# 24ch_amp.net
KiCad netlist of a schematic drawn in EAGLE
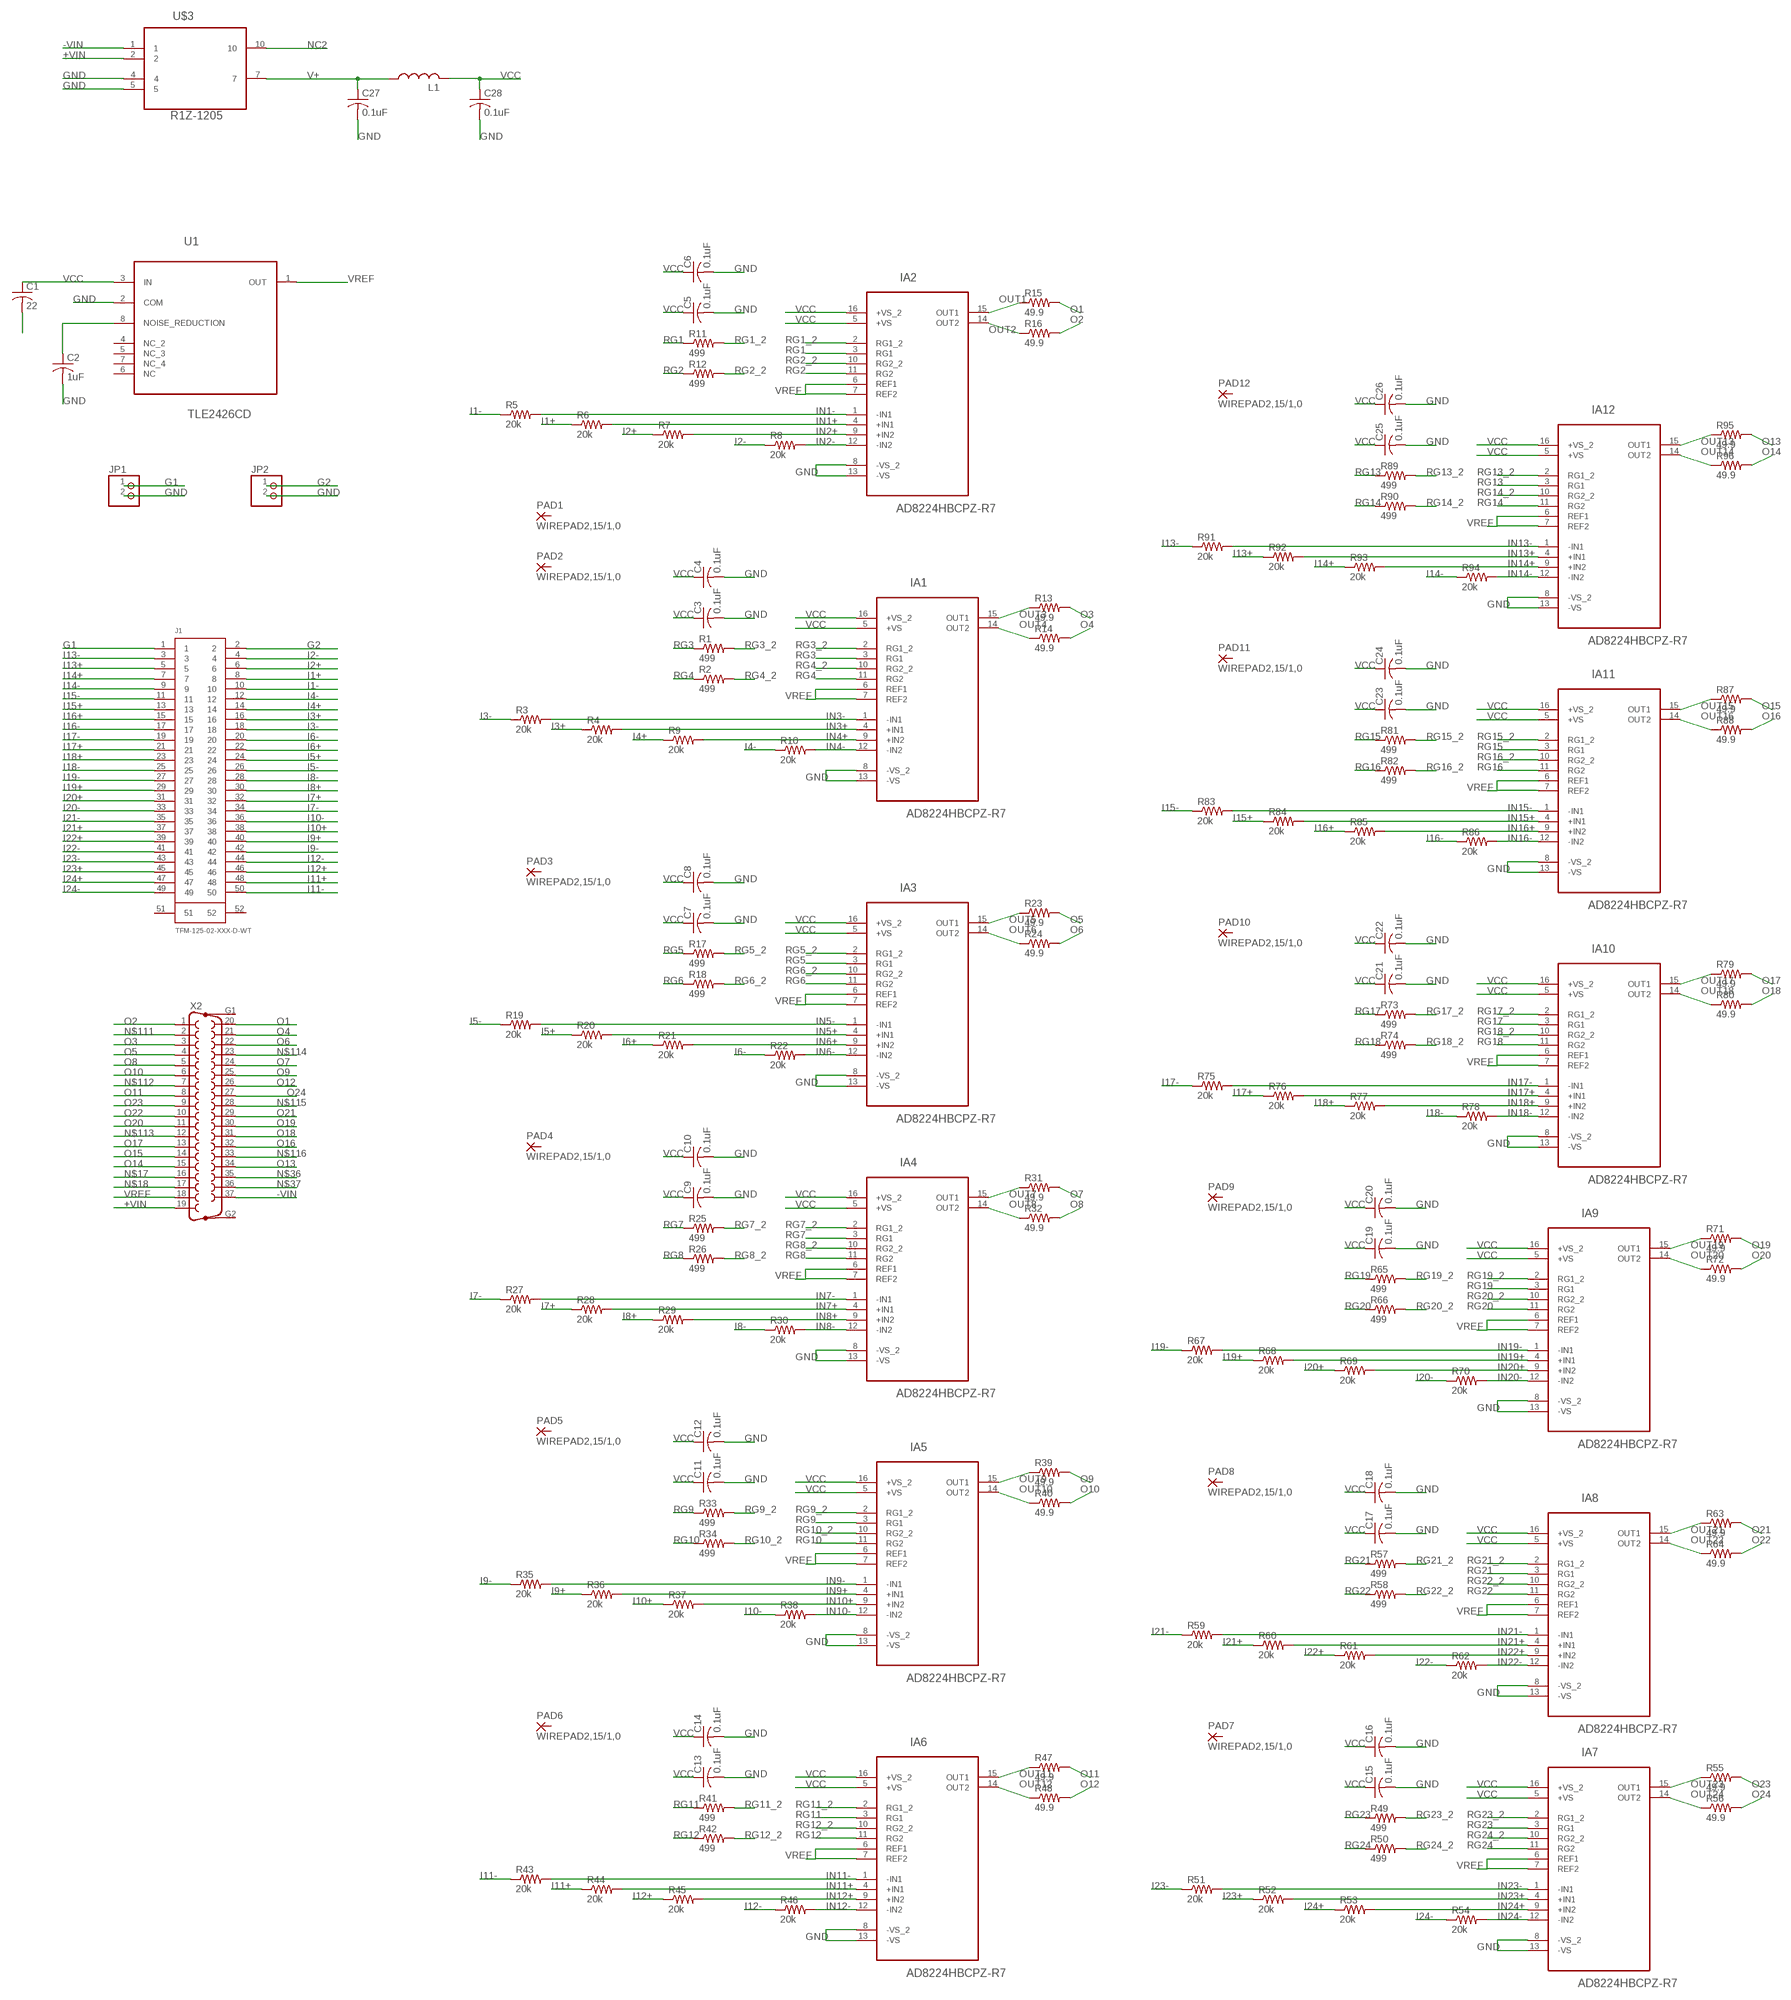
[diagram p0: schematic, sheet 1]

(export (version "E")
  (design (tool "Eeschema 10.0.6"))
  (components
    (comp (ref "C1")
      (value "22")
      (footprint "eagle-import:C0805")
      (libsource (lib "eagle-import") (part "C-USC0805"))
    )
    (comp (ref "C2")
      (value "1uF")
      (footprint "eagle-import:C0805")
      (libsource (lib "eagle-import") (part "C-USC0805"))
    )
    (comp (ref "C3")
      (value "0.1uF")
      (footprint "eagle-import:C0805")
      (libsource (lib "eagle-import") (part "C-USC0805"))
    )
    (comp (ref "C4")
      (value "0.1uF")
      (footprint "eagle-import:C0805")
      (libsource (lib "eagle-import") (part "C-USC0805"))
    )
    (comp (ref "C5")
      (value "0.1uF")
      (footprint "eagle-import:C0805")
      (libsource (lib "eagle-import") (part "C-USC0805"))
    )
    (comp (ref "C6")
      (value "0.1uF")
      (footprint "eagle-import:C0805")
      (libsource (lib "eagle-import") (part "C-USC0805"))
    )
    (comp (ref "C7")
      (value "0.1uF")
      (footprint "eagle-import:C0805")
      (libsource (lib "eagle-import") (part "C-USC0805"))
    )
    (comp (ref "C8")
      (value "0.1uF")
      (footprint "eagle-import:C0805")
      (libsource (lib "eagle-import") (part "C-USC0805"))
    )
    (comp (ref "C9")
      (value "0.1uF")
      (footprint "eagle-import:C0805")
      (libsource (lib "eagle-import") (part "C-USC0805"))
    )
    (comp (ref "C10")
      (value "0.1uF")
      (footprint "eagle-import:C0805")
      (libsource (lib "eagle-import") (part "C-USC0805"))
    )
    (comp (ref "C11")
      (value "0.1uF")
      (footprint "eagle-import:C0805")
      (libsource (lib "eagle-import") (part "C-USC0805"))
    )
    (comp (ref "C12")
      (value "0.1uF")
      (footprint "eagle-import:C0805")
      (libsource (lib "eagle-import") (part "C-USC0805"))
    )
    (comp (ref "C13")
      (value "0.1uF")
      (footprint "eagle-import:C0805")
      (libsource (lib "eagle-import") (part "C-USC0805"))
    )
    (comp (ref "C14")
      (value "0.1uF")
      (footprint "eagle-import:C0805")
      (libsource (lib "eagle-import") (part "C-USC0805"))
    )
    (comp (ref "C15")
      (value "0.1uF")
      (footprint "eagle-import:C0805")
      (libsource (lib "eagle-import") (part "C-USC0805"))
    )
    (comp (ref "C16")
      (value "0.1uF")
      (footprint "eagle-import:C0805")
      (libsource (lib "eagle-import") (part "C-USC0805"))
    )
    (comp (ref "C17")
      (value "0.1uF")
      (footprint "eagle-import:C0805")
      (libsource (lib "eagle-import") (part "C-USC0805"))
    )
    (comp (ref "C18")
      (value "0.1uF")
      (footprint "eagle-import:C0805")
      (libsource (lib "eagle-import") (part "C-USC0805"))
    )
    (comp (ref "C19")
      (value "0.1uF")
      (footprint "eagle-import:C0805")
      (libsource (lib "eagle-import") (part "C-USC0805"))
    )
    (comp (ref "C20")
      (value "0.1uF")
      (footprint "eagle-import:C0805")
      (libsource (lib "eagle-import") (part "C-USC0805"))
    )
    (comp (ref "C21")
      (value "0.1uF")
      (footprint "eagle-import:C0805")
      (libsource (lib "eagle-import") (part "C-USC0805"))
    )
    (comp (ref "C22")
      (value "0.1uF")
      (footprint "eagle-import:C0805")
      (libsource (lib "eagle-import") (part "C-USC0805"))
    )
    (comp (ref "C23")
      (value "0.1uF")
      (footprint "eagle-import:C0805")
      (libsource (lib "eagle-import") (part "C-USC0805"))
    )
    (comp (ref "C24")
      (value "0.1uF")
      (footprint "eagle-import:C0805")
      (libsource (lib "eagle-import") (part "C-USC0805"))
    )
    (comp (ref "C25")
      (value "0.1uF")
      (footprint "eagle-import:C0805")
      (libsource (lib "eagle-import") (part "C-USC0805"))
    )
    (comp (ref "C26")
      (value "0.1uF")
      (footprint "eagle-import:C0805")
      (libsource (lib "eagle-import") (part "C-USC0805"))
    )
    (comp (ref "C27")
      (value "0.1uF")
      (footprint "eagle-import:C0805")
      (libsource (lib "eagle-import") (part "C-USC0805"))
    )
    (comp (ref "C28")
      (value "0.1uF")
      (footprint "eagle-import:C0805")
      (libsource (lib "eagle-import") (part "C-USC0805"))
    )
    (comp (ref "IA1")
      (value "AD8224HBCPZ-R7")
      (footprint "eagle-import:QFN65P400X400X100-16N")
      (libsource (lib "eagle-import") (part "AD8224HBCPZ-R7"))
    )
    (comp (ref "IA2")
      (value "AD8224HBCPZ-R7")
      (footprint "eagle-import:QFN65P400X400X100-16N")
      (libsource (lib "eagle-import") (part "AD8224HBCPZ-R7"))
    )
    (comp (ref "IA3")
      (value "AD8224HBCPZ-R7")
      (footprint "eagle-import:QFN65P400X400X100-16N")
      (libsource (lib "eagle-import") (part "AD8224HBCPZ-R7"))
    )
    (comp (ref "IA4")
      (value "AD8224HBCPZ-R7")
      (footprint "eagle-import:QFN65P400X400X100-16N")
      (libsource (lib "eagle-import") (part "AD8224HBCPZ-R7"))
    )
    (comp (ref "IA5")
      (value "AD8224HBCPZ-R7")
      (footprint "eagle-import:QFN65P400X400X100-16N")
      (libsource (lib "eagle-import") (part "AD8224HBCPZ-R7"))
    )
    (comp (ref "IA6")
      (value "AD8224HBCPZ-R7")
      (footprint "eagle-import:QFN65P400X400X100-16N")
      (libsource (lib "eagle-import") (part "AD8224HBCPZ-R7"))
    )
    (comp (ref "IA7")
      (value "AD8224HBCPZ-R7")
      (footprint "eagle-import:QFN65P400X400X100-16N")
      (libsource (lib "eagle-import") (part "AD8224HBCPZ-R7"))
    )
    (comp (ref "IA8")
      (value "AD8224HBCPZ-R7")
      (footprint "eagle-import:QFN65P400X400X100-16N")
      (libsource (lib "eagle-import") (part "AD8224HBCPZ-R7"))
    )
    (comp (ref "IA9")
      (value "AD8224HBCPZ-R7")
      (footprint "eagle-import:QFN65P400X400X100-16N")
      (libsource (lib "eagle-import") (part "AD8224HBCPZ-R7"))
    )
    (comp (ref "IA10")
      (value "AD8224HBCPZ-R7")
      (footprint "eagle-import:QFN65P400X400X100-16N")
      (libsource (lib "eagle-import") (part "AD8224HBCPZ-R7"))
    )
    (comp (ref "IA11")
      (value "AD8224HBCPZ-R7")
      (footprint "eagle-import:QFN65P400X400X100-16N")
      (libsource (lib "eagle-import") (part "AD8224HBCPZ-R7"))
    )
    (comp (ref "IA12")
      (value "AD8224HBCPZ-R7")
      (footprint "eagle-import:QFN65P400X400X100-16N")
      (libsource (lib "eagle-import") (part "AD8224HBCPZ-R7"))
    )
    (comp (ref "J1")
      (value "TFM-125-02-XXX-D-WT")
      (footprint "eagle-import:TFM-125-02-XXX-D-WT")
      (libsource (lib "eagle-import") (part "TFM-125-02-XXX-D-WT"))
    )
    (comp (ref "JP1")
      (value "PINHD-1X2")
      (footprint "eagle-import:1X02")
      (libsource (lib "eagle-import") (part "PINHD-1X2"))
    )
    (comp (ref "JP2")
      (value "PINHD-1X2")
      (footprint "eagle-import:1X02")
      (libsource (lib "eagle-import") (part "PINHD-1X2"))
    )
    (comp (ref "L1")
      (value "L-USL3225M")
      (footprint "eagle-import:L3225M")
      (libsource (lib "eagle-import") (part "L-USL3225M"))
    )
    (comp (ref "PAD1")
      (value "WIREPAD2,15/1,0")
      (footprint "eagle-import:2,15_1,0")
      (libsource (lib "eagle-import") (part "WIREPAD2,15/1,0"))
    )
    (comp (ref "PAD2")
      (value "WIREPAD2,15/1,0")
      (footprint "eagle-import:2,15_1,0")
      (libsource (lib "eagle-import") (part "WIREPAD2,15/1,0"))
    )
    (comp (ref "PAD3")
      (value "WIREPAD2,15/1,0")
      (footprint "eagle-import:2,15_1,0")
      (libsource (lib "eagle-import") (part "WIREPAD2,15/1,0"))
    )
    (comp (ref "PAD4")
      (value "WIREPAD2,15/1,0")
      (footprint "eagle-import:2,15_1,0")
      (libsource (lib "eagle-import") (part "WIREPAD2,15/1,0"))
    )
    (comp (ref "PAD5")
      (value "WIREPAD2,15/1,0")
      (footprint "eagle-import:2,15_1,0")
      (libsource (lib "eagle-import") (part "WIREPAD2,15/1,0"))
    )
    (comp (ref "PAD6")
      (value "WIREPAD2,15/1,0")
      (footprint "eagle-import:2,15_1,0")
      (libsource (lib "eagle-import") (part "WIREPAD2,15/1,0"))
    )
    (comp (ref "PAD7")
      (value "WIREPAD2,15/1,0")
      (footprint "eagle-import:2,15_1,0")
      (libsource (lib "eagle-import") (part "WIREPAD2,15/1,0"))
    )
    (comp (ref "PAD8")
      (value "WIREPAD2,15/1,0")
      (footprint "eagle-import:2,15_1,0")
      (libsource (lib "eagle-import") (part "WIREPAD2,15/1,0"))
    )
    (comp (ref "PAD9")
      (value "WIREPAD2,15/1,0")
      (footprint "eagle-import:2,15_1,0")
      (libsource (lib "eagle-import") (part "WIREPAD2,15/1,0"))
    )
    (comp (ref "PAD10")
      (value "WIREPAD2,15/1,0")
      (footprint "eagle-import:2,15_1,0")
      (libsource (lib "eagle-import") (part "WIREPAD2,15/1,0"))
    )
    (comp (ref "PAD11")
      (value "WIREPAD2,15/1,0")
      (footprint "eagle-import:2,15_1,0")
      (libsource (lib "eagle-import") (part "WIREPAD2,15/1,0"))
    )
    (comp (ref "PAD12")
      (value "WIREPAD2,15/1,0")
      (footprint "eagle-import:2,15_1,0")
      (libsource (lib "eagle-import") (part "WIREPAD2,15/1,0"))
    )
    (comp (ref "R1")
      (value "499")
      (footprint "eagle-import:R0805")
      (libsource (lib "eagle-import") (part "R-US_R0805"))
    )
    (comp (ref "R2")
      (value "499")
      (footprint "eagle-import:R0805")
      (libsource (lib "eagle-import") (part "R-US_R0805"))
    )
    (comp (ref "R3")
      (value "20k")
      (footprint "eagle-import:R0805")
      (libsource (lib "eagle-import") (part "R-US_R0805"))
    )
    (comp (ref "R4")
      (value "20k")
      (footprint "eagle-import:R0805")
      (libsource (lib "eagle-import") (part "R-US_R0805"))
    )
    (comp (ref "R5")
      (value "20k")
      (footprint "eagle-import:R0805")
      (libsource (lib "eagle-import") (part "R-US_R0805"))
    )
    (comp (ref "R6")
      (value "20k")
      (footprint "eagle-import:R0805")
      (libsource (lib "eagle-import") (part "R-US_R0805"))
    )
    (comp (ref "R7")
      (value "20k")
      (footprint "eagle-import:R0805")
      (libsource (lib "eagle-import") (part "R-US_R0805"))
    )
    (comp (ref "R8")
      (value "20k")
      (footprint "eagle-import:R0805")
      (libsource (lib "eagle-import") (part "R-US_R0805"))
    )
    (comp (ref "R9")
      (value "20k")
      (footprint "eagle-import:R0805")
      (libsource (lib "eagle-import") (part "R-US_R0805"))
    )
    (comp (ref "R10")
      (value "20k")
      (footprint "eagle-import:R0805")
      (libsource (lib "eagle-import") (part "R-US_R0805"))
    )
    (comp (ref "R11")
      (value "499")
      (footprint "eagle-import:R0805")
      (libsource (lib "eagle-import") (part "R-US_R0805"))
    )
    (comp (ref "R12")
      (value "499")
      (footprint "eagle-import:R0805")
      (libsource (lib "eagle-import") (part "R-US_R0805"))
    )
    (comp (ref "R13")
      (value "49.9")
      (footprint "eagle-import:R0805")
      (libsource (lib "eagle-import") (part "R-US_R0805"))
    )
    (comp (ref "R14")
      (value "49.9")
      (footprint "eagle-import:R0805")
      (libsource (lib "eagle-import") (part "R-US_R0805"))
    )
    (comp (ref "R15")
      (value "49.9")
      (footprint "eagle-import:R0805")
      (libsource (lib "eagle-import") (part "R-US_R0805"))
    )
    (comp (ref "R16")
      (value "49.9")
      (footprint "eagle-import:R0805")
      (libsource (lib "eagle-import") (part "R-US_R0805"))
    )
    (comp (ref "R17")
      (value "499")
      (footprint "eagle-import:R0805")
      (libsource (lib "eagle-import") (part "R-US_R0805"))
    )
    (comp (ref "R18")
      (value "499")
      (footprint "eagle-import:R0805")
      (libsource (lib "eagle-import") (part "R-US_R0805"))
    )
    (comp (ref "R19")
      (value "20k")
      (footprint "eagle-import:R0805")
      (libsource (lib "eagle-import") (part "R-US_R0805"))
    )
    (comp (ref "R20")
      (value "20k")
      (footprint "eagle-import:R0805")
      (libsource (lib "eagle-import") (part "R-US_R0805"))
    )
    (comp (ref "R21")
      (value "20k")
      (footprint "eagle-import:R0805")
      (libsource (lib "eagle-import") (part "R-US_R0805"))
    )
    (comp (ref "R22")
      (value "20k")
      (footprint "eagle-import:R0805")
      (libsource (lib "eagle-import") (part "R-US_R0805"))
    )
    (comp (ref "R23")
      (value "49.9")
      (footprint "eagle-import:R0805")
      (libsource (lib "eagle-import") (part "R-US_R0805"))
    )
    (comp (ref "R24")
      (value "49.9")
      (footprint "eagle-import:R0805")
      (libsource (lib "eagle-import") (part "R-US_R0805"))
    )
    (comp (ref "R25")
      (value "499")
      (footprint "eagle-import:R0805")
      (libsource (lib "eagle-import") (part "R-US_R0805"))
    )
    (comp (ref "R26")
      (value "499")
      (footprint "eagle-import:R0805")
      (libsource (lib "eagle-import") (part "R-US_R0805"))
    )
    (comp (ref "R27")
      (value "20k")
      (footprint "eagle-import:R0805")
      (libsource (lib "eagle-import") (part "R-US_R0805"))
    )
    (comp (ref "R28")
      (value "20k")
      (footprint "eagle-import:R0805")
      (libsource (lib "eagle-import") (part "R-US_R0805"))
    )
    (comp (ref "R29")
      (value "20k")
      (footprint "eagle-import:R0805")
      (libsource (lib "eagle-import") (part "R-US_R0805"))
    )
    (comp (ref "R30")
      (value "20k")
      (footprint "eagle-import:R0805")
      (libsource (lib "eagle-import") (part "R-US_R0805"))
    )
    (comp (ref "R31")
      (value "49.9")
      (footprint "eagle-import:R0805")
      (libsource (lib "eagle-import") (part "R-US_R0805"))
    )
    (comp (ref "R32")
      (value "49.9")
      (footprint "eagle-import:R0805")
      (libsource (lib "eagle-import") (part "R-US_R0805"))
    )
    (comp (ref "R33")
      (value "499")
      (footprint "eagle-import:R0805")
      (libsource (lib "eagle-import") (part "R-US_R0805"))
    )
    (comp (ref "R34")
      (value "499")
      (footprint "eagle-import:R0805")
      (libsource (lib "eagle-import") (part "R-US_R0805"))
    )
    (comp (ref "R35")
      (value "20k")
      (footprint "eagle-import:R0805")
      (libsource (lib "eagle-import") (part "R-US_R0805"))
    )
    (comp (ref "R36")
      (value "20k")
      (footprint "eagle-import:R0805")
      (libsource (lib "eagle-import") (part "R-US_R0805"))
    )
    (comp (ref "R37")
      (value "20k")
      (footprint "eagle-import:R0805")
      (libsource (lib "eagle-import") (part "R-US_R0805"))
    )
    (comp (ref "R38")
      (value "20k")
      (footprint "eagle-import:R0805")
      (libsource (lib "eagle-import") (part "R-US_R0805"))
    )
    (comp (ref "R39")
      (value "49.9")
      (footprint "eagle-import:R0805")
      (libsource (lib "eagle-import") (part "R-US_R0805"))
    )
    (comp (ref "R40")
      (value "49.9")
      (footprint "eagle-import:R0805")
      (libsource (lib "eagle-import") (part "R-US_R0805"))
    )
    (comp (ref "R41")
      (value "499")
      (footprint "eagle-import:R0805")
      (libsource (lib "eagle-import") (part "R-US_R0805"))
    )
    (comp (ref "R42")
      (value "499")
      (footprint "eagle-import:R0805")
      (libsource (lib "eagle-import") (part "R-US_R0805"))
    )
    (comp (ref "R43")
      (value "20k")
      (footprint "eagle-import:R0805")
      (libsource (lib "eagle-import") (part "R-US_R0805"))
    )
    (comp (ref "R44")
      (value "20k")
      (footprint "eagle-import:R0805")
      (libsource (lib "eagle-import") (part "R-US_R0805"))
    )
    (comp (ref "R45")
      (value "20k")
      (footprint "eagle-import:R0805")
      (libsource (lib "eagle-import") (part "R-US_R0805"))
    )
    (comp (ref "R46")
      (value "20k")
      (footprint "eagle-import:R0805")
      (libsource (lib "eagle-import") (part "R-US_R0805"))
    )
    (comp (ref "R47")
      (value "49.9")
      (footprint "eagle-import:R0805")
      (libsource (lib "eagle-import") (part "R-US_R0805"))
    )
    (comp (ref "R48")
      (value "49.9")
      (footprint "eagle-import:R0805")
      (libsource (lib "eagle-import") (part "R-US_R0805"))
    )
    (comp (ref "R49")
      (value "499")
      (footprint "eagle-import:R0805")
      (libsource (lib "eagle-import") (part "R-US_R0805"))
    )
    (comp (ref "R50")
      (value "499")
      (footprint "eagle-import:R0805")
      (libsource (lib "eagle-import") (part "R-US_R0805"))
    )
    (comp (ref "R51")
      (value "20k")
      (footprint "eagle-import:R0805")
      (libsource (lib "eagle-import") (part "R-US_R0805"))
    )
    (comp (ref "R52")
      (value "20k")
      (footprint "eagle-import:R0805")
      (libsource (lib "eagle-import") (part "R-US_R0805"))
    )
    (comp (ref "R53")
      (value "20k")
      (footprint "eagle-import:R0805")
      (libsource (lib "eagle-import") (part "R-US_R0805"))
    )
    (comp (ref "R54")
      (value "20k")
      (footprint "eagle-import:R0805")
      (libsource (lib "eagle-import") (part "R-US_R0805"))
    )
    (comp (ref "R55")
      (value "49.9")
      (footprint "eagle-import:R0805")
      (libsource (lib "eagle-import") (part "R-US_R0805"))
    )
    (comp (ref "R56")
      (value "49.9")
      (footprint "eagle-import:R0805")
      (libsource (lib "eagle-import") (part "R-US_R0805"))
    )
    (comp (ref "R57")
      (value "499")
      (footprint "eagle-import:R0805")
      (libsource (lib "eagle-import") (part "R-US_R0805"))
    )
    (comp (ref "R58")
      (value "499")
      (footprint "eagle-import:R0805")
      (libsource (lib "eagle-import") (part "R-US_R0805"))
    )
    (comp (ref "R59")
      (value "20k")
      (footprint "eagle-import:R0805")
      (libsource (lib "eagle-import") (part "R-US_R0805"))
    )
    (comp (ref "R60")
      (value "20k")
      (footprint "eagle-import:R0805")
      (libsource (lib "eagle-import") (part "R-US_R0805"))
    )
    (comp (ref "R61")
      (value "20k")
      (footprint "eagle-import:R0805")
      (libsource (lib "eagle-import") (part "R-US_R0805"))
    )
    (comp (ref "R62")
      (value "20k")
      (footprint "eagle-import:R0805")
      (libsource (lib "eagle-import") (part "R-US_R0805"))
    )
    (comp (ref "R63")
      (value "49.9")
      (footprint "eagle-import:R0805")
      (libsource (lib "eagle-import") (part "R-US_R0805"))
    )
    (comp (ref "R64")
      (value "49.9")
      (footprint "eagle-import:R0805")
      (libsource (lib "eagle-import") (part "R-US_R0805"))
    )
    (comp (ref "R65")
      (value "499")
      (footprint "eagle-import:R0805")
      (libsource (lib "eagle-import") (part "R-US_R0805"))
    )
    (comp (ref "R66")
      (value "499")
      (footprint "eagle-import:R0805")
      (libsource (lib "eagle-import") (part "R-US_R0805"))
    )
    (comp (ref "R67")
      (value "20k")
      (footprint "eagle-import:R0805")
      (libsource (lib "eagle-import") (part "R-US_R0805"))
    )
    (comp (ref "R68")
      (value "20k")
      (footprint "eagle-import:R0805")
      (libsource (lib "eagle-import") (part "R-US_R0805"))
    )
    (comp (ref "R69")
      (value "20k")
      (footprint "eagle-import:R0805")
      (libsource (lib "eagle-import") (part "R-US_R0805"))
    )
    (comp (ref "R70")
      (value "20k")
      (footprint "eagle-import:R0805")
      (libsource (lib "eagle-import") (part "R-US_R0805"))
    )
    (comp (ref "R71")
      (value "49.9")
      (footprint "eagle-import:R0805")
      (libsource (lib "eagle-import") (part "R-US_R0805"))
    )
    (comp (ref "R72")
      (value "49.9")
      (footprint "eagle-import:R0805")
      (libsource (lib "eagle-import") (part "R-US_R0805"))
    )
    (comp (ref "R73")
      (value "499")
      (footprint "eagle-import:R0805")
      (libsource (lib "eagle-import") (part "R-US_R0805"))
    )
    (comp (ref "R74")
      (value "499")
      (footprint "eagle-import:R0805")
      (libsource (lib "eagle-import") (part "R-US_R0805"))
    )
    (comp (ref "R75")
      (value "20k")
      (footprint "eagle-import:R0805")
      (libsource (lib "eagle-import") (part "R-US_R0805"))
    )
    (comp (ref "R76")
      (value "20k")
      (footprint "eagle-import:R0805")
      (libsource (lib "eagle-import") (part "R-US_R0805"))
    )
    (comp (ref "R77")
      (value "20k")
      (footprint "eagle-import:R0805")
      (libsource (lib "eagle-import") (part "R-US_R0805"))
    )
    (comp (ref "R78")
      (value "20k")
      (footprint "eagle-import:R0805")
      (libsource (lib "eagle-import") (part "R-US_R0805"))
    )
    (comp (ref "R79")
      (value "49.9")
      (footprint "eagle-import:R0805")
      (libsource (lib "eagle-import") (part "R-US_R0805"))
    )
    (comp (ref "R80")
      (value "49.9")
      (footprint "eagle-import:R0805")
      (libsource (lib "eagle-import") (part "R-US_R0805"))
    )
    (comp (ref "R81")
      (value "499")
      (footprint "eagle-import:R0805")
      (libsource (lib "eagle-import") (part "R-US_R0805"))
    )
    (comp (ref "R82")
      (value "499")
      (footprint "eagle-import:R0805")
      (libsource (lib "eagle-import") (part "R-US_R0805"))
    )
    (comp (ref "R83")
      (value "20k")
      (footprint "eagle-import:R0805")
      (libsource (lib "eagle-import") (part "R-US_R0805"))
    )
    (comp (ref "R84")
      (value "20k")
      (footprint "eagle-import:R0805")
      (libsource (lib "eagle-import") (part "R-US_R0805"))
    )
    (comp (ref "R85")
      (value "20k")
      (footprint "eagle-import:R0805")
      (libsource (lib "eagle-import") (part "R-US_R0805"))
    )
    (comp (ref "R86")
      (value "20k")
      (footprint "eagle-import:R0805")
      (libsource (lib "eagle-import") (part "R-US_R0805"))
    )
    (comp (ref "R87")
      (value "49.9")
      (footprint "eagle-import:R0805")
      (libsource (lib "eagle-import") (part "R-US_R0805"))
    )
    (comp (ref "R88")
      (value "49.9")
      (footprint "eagle-import:R0805")
      (libsource (lib "eagle-import") (part "R-US_R0805"))
    )
    (comp (ref "R89")
      (value "499")
      (footprint "eagle-import:R0805")
      (libsource (lib "eagle-import") (part "R-US_R0805"))
    )
    (comp (ref "R90")
      (value "499")
      (footprint "eagle-import:R0805")
      (libsource (lib "eagle-import") (part "R-US_R0805"))
    )
    (comp (ref "R91")
      (value "20k")
      (footprint "eagle-import:R0805")
      (libsource (lib "eagle-import") (part "R-US_R0805"))
    )
    (comp (ref "R92")
      (value "20k")
      (footprint "eagle-import:R0805")
      (libsource (lib "eagle-import") (part "R-US_R0805"))
    )
    (comp (ref "R93")
      (value "20k")
      (footprint "eagle-import:R0805")
      (libsource (lib "eagle-import") (part "R-US_R0805"))
    )
    (comp (ref "R94")
      (value "20k")
      (footprint "eagle-import:R0805")
      (libsource (lib "eagle-import") (part "R-US_R0805"))
    )
    (comp (ref "R95")
      (value "49.9")
      (footprint "eagle-import:R0805")
      (libsource (lib "eagle-import") (part "R-US_R0805"))
    )
    (comp (ref "R96")
      (value "49.9")
      (footprint "eagle-import:R0805")
      (libsource (lib "eagle-import") (part "R-US_R0805"))
    )
    (comp (ref "U$3")
      (value "R1Z-1205")
      (footprint "eagle-import:R1Z-1205")
      (libsource (lib "eagle-import") (part "R1Z-1205"))
    )
    (comp (ref "U1")
      (value "TLE2426CD")
      (footprint "eagle-import:SOIC127P600X175-8N")
      (libsource (lib "eagle-import") (part "TLE2426CD"))
    )
    (comp (ref "X2")
      (value "F37HP")
      (footprint "eagle-import:F37HP")
      (libsource (lib "eagle-import") (part "F37HP"))
    )
  )
  (nets
    (net (code "1") (name "/+VIN") (class "Default")
      (node (ref "U$3") (pin "2") (pinfunction "2_2") (pintype "passive"))
      (node (ref "X2") (pin "19") (pinfunction "19_19") (pintype "passive"))
    )
    (net (code "2") (name "/-VIN") (class "Default")
      (node (ref "U$3") (pin "1") (pinfunction "1_1") (pintype "passive"))
      (node (ref "X2") (pin "37") (pinfunction "37_37") (pintype "passive"))
    )
    (net (code "3") (name "/G1") (class "Default")
      (node (ref "J1") (pin "1") (pinfunction "1_1") (pintype "bidirectional"))
      (node (ref "JP1") (pin "1") (pinfunction "1_1") (pintype "passive"))
    )
    (net (code "4") (name "/G2") (class "Default")
      (node (ref "J1") (pin "2") (pinfunction "2_2") (pintype "bidirectional"))
      (node (ref "JP2") (pin "1") (pinfunction "1_1") (pintype "passive"))
    )
    (net (code "5") (name "/GND") (class "Default")
      (node (ref "C1") (pin "2") (pinfunction "2_2") (pintype "passive"))
      (node (ref "C10") (pin "2") (pinfunction "2_2") (pintype "passive"))
      (node (ref "C11") (pin "2") (pinfunction "2_2") (pintype "passive"))
      (node (ref "C12") (pin "2") (pinfunction "2_2") (pintype "passive"))
      (node (ref "C13") (pin "2") (pinfunction "2_2") (pintype "passive"))
      (node (ref "C14") (pin "2") (pinfunction "2_2") (pintype "passive"))
      (node (ref "C15") (pin "2") (pinfunction "2_2") (pintype "passive"))
      (node (ref "C16") (pin "2") (pinfunction "2_2") (pintype "passive"))
      (node (ref "C17") (pin "2") (pinfunction "2_2") (pintype "passive"))
      (node (ref "C18") (pin "2") (pinfunction "2_2") (pintype "passive"))
      (node (ref "C19") (pin "2") (pinfunction "2_2") (pintype "passive"))
      (node (ref "C2") (pin "2") (pinfunction "2_2") (pintype "passive"))
      (node (ref "C20") (pin "2") (pinfunction "2_2") (pintype "passive"))
      (node (ref "C21") (pin "2") (pinfunction "2_2") (pintype "passive"))
      (node (ref "C22") (pin "2") (pinfunction "2_2") (pintype "passive"))
      (node (ref "C23") (pin "2") (pinfunction "2_2") (pintype "passive"))
      (node (ref "C24") (pin "2") (pinfunction "2_2") (pintype "passive"))
      (node (ref "C25") (pin "2") (pinfunction "2_2") (pintype "passive"))
      (node (ref "C26") (pin "2") (pinfunction "2_2") (pintype "passive"))
      (node (ref "C27") (pin "2") (pinfunction "2_2") (pintype "passive"))
      (node (ref "C28") (pin "2") (pinfunction "2_2") (pintype "passive"))
      (node (ref "C3") (pin "2") (pinfunction "2_2") (pintype "passive"))
      (node (ref "C4") (pin "2") (pinfunction "2_2") (pintype "passive"))
      (node (ref "C5") (pin "2") (pinfunction "2_2") (pintype "passive"))
      (node (ref "C6") (pin "2") (pinfunction "2_2") (pintype "passive"))
      (node (ref "C7") (pin "2") (pinfunction "2_2") (pintype "passive"))
      (node (ref "C8") (pin "2") (pinfunction "2_2") (pintype "passive"))
      (node (ref "C9") (pin "2") (pinfunction "2_2") (pintype "passive"))
      (node (ref "IA1") (pin "13") (pinfunction "-VS_13") (pintype "power_in"))
      (node (ref "IA1") (pin "8") (pinfunction "-VS_2_8") (pintype "power_in"))
      (node (ref "IA10") (pin "13") (pinfunction "-VS_13") (pintype "power_in"))
      (node (ref "IA10") (pin "8") (pinfunction "-VS_2_8") (pintype "power_in"))
      (node (ref "IA11") (pin "13") (pinfunction "-VS_13") (pintype "power_in"))
      (node (ref "IA11") (pin "8") (pinfunction "-VS_2_8") (pintype "power_in"))
      (node (ref "IA12") (pin "13") (pinfunction "-VS_13") (pintype "power_in"))
      (node (ref "IA12") (pin "8") (pinfunction "-VS_2_8") (pintype "power_in"))
      (node (ref "IA2") (pin "13") (pinfunction "-VS_13") (pintype "power_in"))
      (node (ref "IA2") (pin "8") (pinfunction "-VS_2_8") (pintype "power_in"))
      (node (ref "IA3") (pin "13") (pinfunction "-VS_13") (pintype "power_in"))
      (node (ref "IA3") (pin "8") (pinfunction "-VS_2_8") (pintype "power_in"))
      (node (ref "IA4") (pin "13") (pinfunction "-VS_13") (pintype "power_in"))
      (node (ref "IA4") (pin "8") (pinfunction "-VS_2_8") (pintype "power_in"))
      (node (ref "IA5") (pin "13") (pinfunction "-VS_13") (pintype "power_in"))
      (node (ref "IA5") (pin "8") (pinfunction "-VS_2_8") (pintype "power_in"))
      (node (ref "IA6") (pin "13") (pinfunction "-VS_13") (pintype "power_in"))
      (node (ref "IA6") (pin "8") (pinfunction "-VS_2_8") (pintype "power_in"))
      (node (ref "IA7") (pin "13") (pinfunction "-VS_13") (pintype "power_in"))
      (node (ref "IA7") (pin "8") (pinfunction "-VS_2_8") (pintype "power_in"))
      (node (ref "IA8") (pin "13") (pinfunction "-VS_13") (pintype "power_in"))
      (node (ref "IA8") (pin "8") (pinfunction "-VS_2_8") (pintype "power_in"))
      (node (ref "IA9") (pin "13") (pinfunction "-VS_13") (pintype "power_in"))
      (node (ref "IA9") (pin "8") (pinfunction "-VS_2_8") (pintype "power_in"))
      (node (ref "JP1") (pin "2") (pinfunction "2_2") (pintype "passive"))
      (node (ref "JP2") (pin "2") (pinfunction "2_2") (pintype "passive"))
      (node (ref "U$3") (pin "4") (pinfunction "4_4") (pintype "passive"))
      (node (ref "U$3") (pin "5") (pinfunction "5_5") (pintype "passive"))
      (node (ref "U1") (pin "2") (pinfunction "COM_2") (pintype "passive"))
    )
    (net (code "6") (name "/I1+") (class "Default")
      (node (ref "J1") (pin "8") (pinfunction "8_8") (pintype "bidirectional"))
      (node (ref "R6") (pin "1") (pinfunction "1_1") (pintype "passive"))
    )
    (net (code "7") (name "/I1-") (class "Default")
      (node (ref "J1") (pin "10") (pinfunction "10_10") (pintype "bidirectional"))
      (node (ref "R5") (pin "1") (pinfunction "1_1") (pintype "passive"))
    )
    (net (code "8") (name "/I2+") (class "Default")
      (node (ref "J1") (pin "6") (pinfunction "6_6") (pintype "bidirectional"))
      (node (ref "R7") (pin "1") (pinfunction "1_1") (pintype "passive"))
    )
    (net (code "9") (name "/I2-") (class "Default")
      (node (ref "J1") (pin "4") (pinfunction "4_4") (pintype "bidirectional"))
      (node (ref "R8") (pin "1") (pinfunction "1_1") (pintype "passive"))
    )
    (net (code "10") (name "/I3+") (class "Default")
      (node (ref "J1") (pin "16") (pinfunction "16_16") (pintype "bidirectional"))
      (node (ref "R4") (pin "1") (pinfunction "1_1") (pintype "passive"))
    )
    (net (code "11") (name "/I3-") (class "Default")
      (node (ref "J1") (pin "18") (pinfunction "18_18") (pintype "bidirectional"))
      (node (ref "R3") (pin "1") (pinfunction "1_1") (pintype "passive"))
    )
    (net (code "12") (name "/I4+") (class "Default")
      (node (ref "J1") (pin "14") (pinfunction "14_14") (pintype "bidirectional"))
      (node (ref "R9") (pin "1") (pinfunction "1_1") (pintype "passive"))
    )
    (net (code "13") (name "/I4-") (class "Default")
      (node (ref "J1") (pin "12") (pinfunction "12_12") (pintype "bidirectional"))
      (node (ref "R10") (pin "1") (pinfunction "1_1") (pintype "passive"))
    )
    (net (code "14") (name "/I5+") (class "Default")
      (node (ref "J1") (pin "24") (pinfunction "24_24") (pintype "bidirectional"))
      (node (ref "R20") (pin "1") (pinfunction "1_1") (pintype "passive"))
    )
    (net (code "15") (name "/I5-") (class "Default")
      (node (ref "J1") (pin "26") (pinfunction "26_26") (pintype "bidirectional"))
      (node (ref "R19") (pin "1") (pinfunction "1_1") (pintype "passive"))
    )
    (net (code "16") (name "/I6+") (class "Default")
      (node (ref "J1") (pin "22") (pinfunction "22_22") (pintype "bidirectional"))
      (node (ref "R21") (pin "1") (pinfunction "1_1") (pintype "passive"))
    )
    (net (code "17") (name "/I6-") (class "Default")
      (node (ref "J1") (pin "20") (pinfunction "20_20") (pintype "bidirectional"))
      (node (ref "R22") (pin "1") (pinfunction "1_1") (pintype "passive"))
    )
    (net (code "18") (name "/I7+") (class "Default")
      (node (ref "J1") (pin "32") (pinfunction "32_32") (pintype "bidirectional"))
      (node (ref "R28") (pin "1") (pinfunction "1_1") (pintype "passive"))
    )
    (net (code "19") (name "/I7-") (class "Default")
      (node (ref "J1") (pin "34") (pinfunction "34_34") (pintype "bidirectional"))
      (node (ref "R27") (pin "1") (pinfunction "1_1") (pintype "passive"))
    )
    (net (code "20") (name "/I8+") (class "Default")
      (node (ref "J1") (pin "30") (pinfunction "30_30") (pintype "bidirectional"))
      (node (ref "R29") (pin "1") (pinfunction "1_1") (pintype "passive"))
    )
    (net (code "21") (name "/I8-") (class "Default")
      (node (ref "J1") (pin "28") (pinfunction "28_28") (pintype "bidirectional"))
      (node (ref "R30") (pin "1") (pinfunction "1_1") (pintype "passive"))
    )
    (net (code "22") (name "/I9+") (class "Default")
      (node (ref "J1") (pin "40") (pinfunction "40_40") (pintype "bidirectional"))
      (node (ref "R36") (pin "1") (pinfunction "1_1") (pintype "passive"))
    )
    (net (code "23") (name "/I9-") (class "Default")
      (node (ref "J1") (pin "42") (pinfunction "42_42") (pintype "bidirectional"))
      (node (ref "R35") (pin "1") (pinfunction "1_1") (pintype "passive"))
    )
    (net (code "24") (name "/I10+") (class "Default")
      (node (ref "J1") (pin "38") (pinfunction "38_38") (pintype "bidirectional"))
      (node (ref "R37") (pin "1") (pinfunction "1_1") (pintype "passive"))
    )
    (net (code "25") (name "/I10-") (class "Default")
      (node (ref "J1") (pin "36") (pinfunction "36_36") (pintype "bidirectional"))
      (node (ref "R38") (pin "1") (pinfunction "1_1") (pintype "passive"))
    )
    (net (code "26") (name "/I11+") (class "Default")
      (node (ref "J1") (pin "48") (pinfunction "48_48") (pintype "bidirectional"))
      (node (ref "R44") (pin "1") (pinfunction "1_1") (pintype "passive"))
    )
    (net (code "27") (name "/I11-") (class "Default")
      (node (ref "J1") (pin "50") (pinfunction "50_50") (pintype "bidirectional"))
      (node (ref "R43") (pin "1") (pinfunction "1_1") (pintype "passive"))
    )
    (net (code "28") (name "/I12+") (class "Default")
      (node (ref "J1") (pin "46") (pinfunction "46_46") (pintype "bidirectional"))
      (node (ref "R45") (pin "1") (pinfunction "1_1") (pintype "passive"))
    )
    (net (code "29") (name "/I12-") (class "Default")
      (node (ref "J1") (pin "44") (pinfunction "44_44") (pintype "bidirectional"))
      (node (ref "R46") (pin "1") (pinfunction "1_1") (pintype "passive"))
    )
    (net (code "30") (name "/I13+") (class "Default")
      (node (ref "J1") (pin "5") (pinfunction "5_5") (pintype "bidirectional"))
      (node (ref "R92") (pin "1") (pinfunction "1_1") (pintype "passive"))
    )
    (net (code "31") (name "/I13-") (class "Default")
      (node (ref "J1") (pin "3") (pinfunction "3_3") (pintype "bidirectional"))
      (node (ref "R91") (pin "1") (pinfunction "1_1") (pintype "passive"))
    )
    (net (code "32") (name "/I14+") (class "Default")
      (node (ref "J1") (pin "7") (pinfunction "7_7") (pintype "bidirectional"))
      (node (ref "R93") (pin "1") (pinfunction "1_1") (pintype "passive"))
    )
    (net (code "33") (name "/I14-") (class "Default")
      (node (ref "J1") (pin "9") (pinfunction "9_9") (pintype "bidirectional"))
      (node (ref "R94") (pin "1") (pinfunction "1_1") (pintype "passive"))
    )
    (net (code "34") (name "/I15+") (class "Default")
      (node (ref "J1") (pin "13") (pinfunction "13_13") (pintype "bidirectional"))
      (node (ref "R84") (pin "1") (pinfunction "1_1") (pintype "passive"))
    )
    (net (code "35") (name "/I15-") (class "Default")
      (node (ref "J1") (pin "11") (pinfunction "11_11") (pintype "bidirectional"))
      (node (ref "R83") (pin "1") (pinfunction "1_1") (pintype "passive"))
    )
    (net (code "36") (name "/I16+") (class "Default")
      (node (ref "J1") (pin "15") (pinfunction "15_15") (pintype "bidirectional"))
      (node (ref "R85") (pin "1") (pinfunction "1_1") (pintype "passive"))
    )
    (net (code "37") (name "/I16-") (class "Default")
      (node (ref "J1") (pin "17") (pinfunction "17_17") (pintype "bidirectional"))
      (node (ref "R86") (pin "1") (pinfunction "1_1") (pintype "passive"))
    )
    (net (code "38") (name "/I17+") (class "Default")
      (node (ref "J1") (pin "21") (pinfunction "21_21") (pintype "bidirectional"))
      (node (ref "R76") (pin "1") (pinfunction "1_1") (pintype "passive"))
    )
    (net (code "39") (name "/I17-") (class "Default")
      (node (ref "J1") (pin "19") (pinfunction "19_19") (pintype "bidirectional"))
      (node (ref "R75") (pin "1") (pinfunction "1_1") (pintype "passive"))
    )
    (net (code "40") (name "/I18+") (class "Default")
      (node (ref "J1") (pin "23") (pinfunction "23_23") (pintype "bidirectional"))
      (node (ref "R77") (pin "1") (pinfunction "1_1") (pintype "passive"))
    )
    (net (code "41") (name "/I18-") (class "Default")
      (node (ref "J1") (pin "25") (pinfunction "25_25") (pintype "bidirectional"))
      (node (ref "R78") (pin "1") (pinfunction "1_1") (pintype "passive"))
    )
    (net (code "42") (name "/I19+") (class "Default")
      (node (ref "J1") (pin "29") (pinfunction "29_29") (pintype "bidirectional"))
      (node (ref "R68") (pin "1") (pinfunction "1_1") (pintype "passive"))
    )
    (net (code "43") (name "/I19-") (class "Default")
      (node (ref "J1") (pin "27") (pinfunction "27_27") (pintype "bidirectional"))
      (node (ref "R67") (pin "1") (pinfunction "1_1") (pintype "passive"))
    )
    (net (code "44") (name "/I20+") (class "Default")
      (node (ref "J1") (pin "31") (pinfunction "31_31") (pintype "bidirectional"))
      (node (ref "R69") (pin "1") (pinfunction "1_1") (pintype "passive"))
    )
    (net (code "45") (name "/I20-") (class "Default")
      (node (ref "J1") (pin "33") (pinfunction "33_33") (pintype "bidirectional"))
      (node (ref "R70") (pin "1") (pinfunction "1_1") (pintype "passive"))
    )
    (net (code "46") (name "/I21+") (class "Default")
      (node (ref "J1") (pin "37") (pinfunction "37_37") (pintype "bidirectional"))
      (node (ref "R60") (pin "1") (pinfunction "1_1") (pintype "passive"))
    )
    (net (code "47") (name "/I21-") (class "Default")
      (node (ref "J1") (pin "35") (pinfunction "35_35") (pintype "bidirectional"))
      (node (ref "R59") (pin "1") (pinfunction "1_1") (pintype "passive"))
    )
    (net (code "48") (name "/I22+") (class "Default")
      (node (ref "J1") (pin "39") (pinfunction "39_39") (pintype "bidirectional"))
      (node (ref "R61") (pin "1") (pinfunction "1_1") (pintype "passive"))
    )
    (net (code "49") (name "/I22-") (class "Default")
      (node (ref "J1") (pin "41") (pinfunction "41_41") (pintype "bidirectional"))
      (node (ref "R62") (pin "1") (pinfunction "1_1") (pintype "passive"))
    )
    (net (code "50") (name "/I23+") (class "Default")
      (node (ref "J1") (pin "45") (pinfunction "45_45") (pintype "bidirectional"))
      (node (ref "R52") (pin "1") (pinfunction "1_1") (pintype "passive"))
    )
    (net (code "51") (name "/I23-") (class "Default")
      (node (ref "J1") (pin "43") (pinfunction "43_43") (pintype "bidirectional"))
      (node (ref "R51") (pin "1") (pinfunction "1_1") (pintype "passive"))
    )
    (net (code "52") (name "/I24+") (class "Default")
      (node (ref "J1") (pin "47") (pinfunction "47_47") (pintype "bidirectional"))
      (node (ref "R53") (pin "1") (pinfunction "1_1") (pintype "passive"))
    )
    (net (code "53") (name "/I24-") (class "Default")
      (node (ref "J1") (pin "49") (pinfunction "49_49") (pintype "bidirectional"))
      (node (ref "R54") (pin "1") (pinfunction "1_1") (pintype "passive"))
    )
    (net (code "54") (name "/IN1+") (class "Default")
      (node (ref "IA2") (pin "4") (pinfunction "+IN1_4") (pintype "input"))
      (node (ref "R6") (pin "2") (pinfunction "2_2") (pintype "passive"))
    )
    (net (code "55") (name "/IN1-") (class "Default")
      (node (ref "IA2") (pin "1") (pinfunction "-IN1_1") (pintype "input"))
      (node (ref "R5") (pin "2") (pinfunction "2_2") (pintype "passive"))
    )
    (net (code "56") (name "/IN2+") (class "Default")
      (node (ref "IA2") (pin "9") (pinfunction "+IN2_9") (pintype "input"))
      (node (ref "R7") (pin "2") (pinfunction "2_2") (pintype "passive"))
    )
    (net (code "57") (name "/IN2-") (class "Default")
      (node (ref "IA2") (pin "12") (pinfunction "-IN2_12") (pintype "input"))
      (node (ref "R8") (pin "2") (pinfunction "2_2") (pintype "passive"))
    )
    (net (code "58") (name "/IN3+") (class "Default")
      (node (ref "IA1") (pin "4") (pinfunction "+IN1_4") (pintype "input"))
      (node (ref "R4") (pin "2") (pinfunction "2_2") (pintype "passive"))
    )
    (net (code "59") (name "/IN3-") (class "Default")
      (node (ref "IA1") (pin "1") (pinfunction "-IN1_1") (pintype "input"))
      (node (ref "R3") (pin "2") (pinfunction "2_2") (pintype "passive"))
    )
    (net (code "60") (name "/IN4+") (class "Default")
      (node (ref "IA1") (pin "9") (pinfunction "+IN2_9") (pintype "input"))
      (node (ref "R9") (pin "2") (pinfunction "2_2") (pintype "passive"))
    )
    (net (code "61") (name "/IN4-") (class "Default")
      (node (ref "IA1") (pin "12") (pinfunction "-IN2_12") (pintype "input"))
      (node (ref "R10") (pin "2") (pinfunction "2_2") (pintype "passive"))
    )
    (net (code "62") (name "/IN5+") (class "Default")
      (node (ref "IA3") (pin "4") (pinfunction "+IN1_4") (pintype "input"))
      (node (ref "R20") (pin "2") (pinfunction "2_2") (pintype "passive"))
    )
    (net (code "63") (name "/IN5-") (class "Default")
      (node (ref "IA3") (pin "1") (pinfunction "-IN1_1") (pintype "input"))
      (node (ref "R19") (pin "2") (pinfunction "2_2") (pintype "passive"))
    )
    (net (code "64") (name "/IN6+") (class "Default")
      (node (ref "IA3") (pin "9") (pinfunction "+IN2_9") (pintype "input"))
      (node (ref "R21") (pin "2") (pinfunction "2_2") (pintype "passive"))
    )
    (net (code "65") (name "/IN6-") (class "Default")
      (node (ref "IA3") (pin "12") (pinfunction "-IN2_12") (pintype "input"))
      (node (ref "R22") (pin "2") (pinfunction "2_2") (pintype "passive"))
    )
    (net (code "66") (name "/IN7+") (class "Default")
      (node (ref "IA4") (pin "4") (pinfunction "+IN1_4") (pintype "input"))
      (node (ref "R28") (pin "2") (pinfunction "2_2") (pintype "passive"))
    )
    (net (code "67") (name "/IN7-") (class "Default")
      (node (ref "IA4") (pin "1") (pinfunction "-IN1_1") (pintype "input"))
      (node (ref "R27") (pin "2") (pinfunction "2_2") (pintype "passive"))
    )
    (net (code "68") (name "/IN8+") (class "Default")
      (node (ref "IA4") (pin "9") (pinfunction "+IN2_9") (pintype "input"))
      (node (ref "R29") (pin "2") (pinfunction "2_2") (pintype "passive"))
    )
    (net (code "69") (name "/IN8-") (class "Default")
      (node (ref "IA4") (pin "12") (pinfunction "-IN2_12") (pintype "input"))
      (node (ref "R30") (pin "2") (pinfunction "2_2") (pintype "passive"))
    )
    (net (code "70") (name "/IN9+") (class "Default")
      (node (ref "IA5") (pin "4") (pinfunction "+IN1_4") (pintype "input"))
      (node (ref "R36") (pin "2") (pinfunction "2_2") (pintype "passive"))
    )
    (net (code "71") (name "/IN9-") (class "Default")
      (node (ref "IA5") (pin "1") (pinfunction "-IN1_1") (pintype "input"))
      (node (ref "R35") (pin "2") (pinfunction "2_2") (pintype "passive"))
    )
    (net (code "72") (name "/IN10+") (class "Default")
      (node (ref "IA5") (pin "9") (pinfunction "+IN2_9") (pintype "input"))
      (node (ref "R37") (pin "2") (pinfunction "2_2") (pintype "passive"))
    )
    (net (code "73") (name "/IN10-") (class "Default")
      (node (ref "IA5") (pin "12") (pinfunction "-IN2_12") (pintype "input"))
      (node (ref "R38") (pin "2") (pinfunction "2_2") (pintype "passive"))
    )
    (net (code "74") (name "/IN11+") (class "Default")
      (node (ref "IA6") (pin "4") (pinfunction "+IN1_4") (pintype "input"))
      (node (ref "R44") (pin "2") (pinfunction "2_2") (pintype "passive"))
    )
    (net (code "75") (name "/IN11-") (class "Default")
      (node (ref "IA6") (pin "1") (pinfunction "-IN1_1") (pintype "input"))
      (node (ref "R43") (pin "2") (pinfunction "2_2") (pintype "passive"))
    )
    (net (code "76") (name "/IN12+") (class "Default")
      (node (ref "IA6") (pin "9") (pinfunction "+IN2_9") (pintype "input"))
      (node (ref "R45") (pin "2") (pinfunction "2_2") (pintype "passive"))
    )
    (net (code "77") (name "/IN12-") (class "Default")
      (node (ref "IA6") (pin "12") (pinfunction "-IN2_12") (pintype "input"))
      (node (ref "R46") (pin "2") (pinfunction "2_2") (pintype "passive"))
    )
    (net (code "78") (name "/IN13+") (class "Default")
      (node (ref "IA12") (pin "4") (pinfunction "+IN1_4") (pintype "input"))
      (node (ref "R92") (pin "2") (pinfunction "2_2") (pintype "passive"))
    )
    (net (code "79") (name "/IN13-") (class "Default")
      (node (ref "IA12") (pin "1") (pinfunction "-IN1_1") (pintype "input"))
      (node (ref "R91") (pin "2") (pinfunction "2_2") (pintype "passive"))
    )
    (net (code "80") (name "/IN14+") (class "Default")
      (node (ref "IA12") (pin "9") (pinfunction "+IN2_9") (pintype "input"))
      (node (ref "R93") (pin "2") (pinfunction "2_2") (pintype "passive"))
    )
    (net (code "81") (name "/IN14-") (class "Default")
      (node (ref "IA12") (pin "12") (pinfunction "-IN2_12") (pintype "input"))
      (node (ref "R94") (pin "2") (pinfunction "2_2") (pintype "passive"))
    )
    (net (code "82") (name "/IN15+") (class "Default")
      (node (ref "IA11") (pin "4") (pinfunction "+IN1_4") (pintype "input"))
      (node (ref "R84") (pin "2") (pinfunction "2_2") (pintype "passive"))
    )
    (net (code "83") (name "/IN15-") (class "Default")
      (node (ref "IA11") (pin "1") (pinfunction "-IN1_1") (pintype "input"))
      (node (ref "R83") (pin "2") (pinfunction "2_2") (pintype "passive"))
    )
    (net (code "84") (name "/IN16+") (class "Default")
      (node (ref "IA11") (pin "9") (pinfunction "+IN2_9") (pintype "input"))
      (node (ref "R85") (pin "2") (pinfunction "2_2") (pintype "passive"))
    )
    (net (code "85") (name "/IN16-") (class "Default")
      (node (ref "IA11") (pin "12") (pinfunction "-IN2_12") (pintype "input"))
      (node (ref "R86") (pin "2") (pinfunction "2_2") (pintype "passive"))
    )
    (net (code "86") (name "/IN17+") (class "Default")
      (node (ref "IA10") (pin "4") (pinfunction "+IN1_4") (pintype "input"))
      (node (ref "R76") (pin "2") (pinfunction "2_2") (pintype "passive"))
    )
    (net (code "87") (name "/IN17-") (class "Default")
      (node (ref "IA10") (pin "1") (pinfunction "-IN1_1") (pintype "input"))
      (node (ref "R75") (pin "2") (pinfunction "2_2") (pintype "passive"))
    )
    (net (code "88") (name "/IN18+") (class "Default")
      (node (ref "IA10") (pin "9") (pinfunction "+IN2_9") (pintype "input"))
      (node (ref "R77") (pin "2") (pinfunction "2_2") (pintype "passive"))
    )
    (net (code "89") (name "/IN18-") (class "Default")
      (node (ref "IA10") (pin "12") (pinfunction "-IN2_12") (pintype "input"))
      (node (ref "R78") (pin "2") (pinfunction "2_2") (pintype "passive"))
    )
    (net (code "90") (name "/IN19+") (class "Default")
      (node (ref "IA9") (pin "4") (pinfunction "+IN1_4") (pintype "input"))
      (node (ref "R68") (pin "2") (pinfunction "2_2") (pintype "passive"))
    )
    (net (code "91") (name "/IN19-") (class "Default")
      (node (ref "IA9") (pin "1") (pinfunction "-IN1_1") (pintype "input"))
      (node (ref "R67") (pin "2") (pinfunction "2_2") (pintype "passive"))
    )
    (net (code "92") (name "/IN20+") (class "Default")
      (node (ref "IA9") (pin "9") (pinfunction "+IN2_9") (pintype "input"))
      (node (ref "R69") (pin "2") (pinfunction "2_2") (pintype "passive"))
    )
    (net (code "93") (name "/IN20-") (class "Default")
      (node (ref "IA9") (pin "12") (pinfunction "-IN2_12") (pintype "input"))
      (node (ref "R70") (pin "2") (pinfunction "2_2") (pintype "passive"))
    )
    (net (code "94") (name "/IN21+") (class "Default")
      (node (ref "IA8") (pin "4") (pinfunction "+IN1_4") (pintype "input"))
      (node (ref "R60") (pin "2") (pinfunction "2_2") (pintype "passive"))
    )
    (net (code "95") (name "/IN21-") (class "Default")
      (node (ref "IA8") (pin "1") (pinfunction "-IN1_1") (pintype "input"))
      (node (ref "R59") (pin "2") (pinfunction "2_2") (pintype "passive"))
    )
    (net (code "96") (name "/IN22+") (class "Default")
      (node (ref "IA8") (pin "9") (pinfunction "+IN2_9") (pintype "input"))
      (node (ref "R61") (pin "2") (pinfunction "2_2") (pintype "passive"))
    )
    (net (code "97") (name "/IN22-") (class "Default")
      (node (ref "IA8") (pin "12") (pinfunction "-IN2_12") (pintype "input"))
      (node (ref "R62") (pin "2") (pinfunction "2_2") (pintype "passive"))
    )
    (net (code "98") (name "/IN23+") (class "Default")
      (node (ref "IA7") (pin "4") (pinfunction "+IN1_4") (pintype "input"))
      (node (ref "R52") (pin "2") (pinfunction "2_2") (pintype "passive"))
    )
    (net (code "99") (name "/IN23-") (class "Default")
      (node (ref "IA7") (pin "1") (pinfunction "-IN1_1") (pintype "input"))
      (node (ref "R51") (pin "2") (pinfunction "2_2") (pintype "passive"))
    )
    (net (code "100") (name "/IN24+") (class "Default")
      (node (ref "IA7") (pin "9") (pinfunction "+IN2_9") (pintype "input"))
      (node (ref "R53") (pin "2") (pinfunction "2_2") (pintype "passive"))
    )
    (net (code "101") (name "/IN24-") (class "Default")
      (node (ref "IA7") (pin "12") (pinfunction "-IN2_12") (pintype "input"))
      (node (ref "R54") (pin "2") (pinfunction "2_2") (pintype "passive"))
    )
    (net (code "102") (name "/N$17") (class "Default")
      (node (ref "X2") (pin "16") (pinfunction "16_16") (pintype "passive"))
    )
    (net (code "103") (name "/N$18") (class "Default")
      (node (ref "X2") (pin "17") (pinfunction "17_17") (pintype "passive"))
    )
    (net (code "104") (name "/N$36") (class "Default")
      (node (ref "X2") (pin "35") (pinfunction "35_35") (pintype "passive"))
    )
    (net (code "105") (name "/N$37") (class "Default")
      (node (ref "X2") (pin "36") (pinfunction "36_36") (pintype "passive"))
    )
    (net (code "106") (name "/N$111") (class "Default")
      (node (ref "X2") (pin "2") (pinfunction "2_2") (pintype "passive"))
    )
    (net (code "107") (name "/N$112") (class "Default")
      (node (ref "X2") (pin "7") (pinfunction "7_7") (pintype "passive"))
    )
    (net (code "108") (name "/N$113") (class "Default")
      (node (ref "X2") (pin "12") (pinfunction "12_12") (pintype "passive"))
    )
    (net (code "109") (name "/N$114") (class "Default")
      (node (ref "X2") (pin "23") (pinfunction "23_23") (pintype "passive"))
    )
    (net (code "110") (name "/N$115") (class "Default")
      (node (ref "X2") (pin "28") (pinfunction "28_28") (pintype "passive"))
    )
    (net (code "111") (name "/N$116") (class "Default")
      (node (ref "X2") (pin "33") (pinfunction "33_33") (pintype "passive"))
    )
    (net (code "112") (name "/NC2") (class "Default")
      (node (ref "U$3") (pin "10") (pinfunction "10_10") (pintype "passive"))
    )
    (net (code "113") (name "/O1") (class "Default")
      (node (ref "R15") (pin "2") (pinfunction "2_2") (pintype "passive"))
      (node (ref "X2") (pin "20") (pinfunction "20_20") (pintype "passive"))
    )
    (net (code "114") (name "/O2") (class "Default")
      (node (ref "R16") (pin "2") (pinfunction "2_2") (pintype "passive"))
      (node (ref "X2") (pin "1") (pinfunction "1_1") (pintype "passive"))
    )
    (net (code "115") (name "/O3") (class "Default")
      (node (ref "R13") (pin "2") (pinfunction "2_2") (pintype "passive"))
      (node (ref "X2") (pin "3") (pinfunction "3_3") (pintype "passive"))
    )
    (net (code "116") (name "/O4") (class "Default")
      (node (ref "R14") (pin "2") (pinfunction "2_2") (pintype "passive"))
      (node (ref "X2") (pin "21") (pinfunction "21_21") (pintype "passive"))
    )
    (net (code "117") (name "/O5") (class "Default")
      (node (ref "R23") (pin "2") (pinfunction "2_2") (pintype "passive"))
      (node (ref "X2") (pin "4") (pinfunction "4_4") (pintype "passive"))
    )
    (net (code "118") (name "/O6") (class "Default")
      (node (ref "R24") (pin "2") (pinfunction "2_2") (pintype "passive"))
      (node (ref "X2") (pin "22") (pinfunction "22_22") (pintype "passive"))
    )
    (net (code "119") (name "/O7") (class "Default")
      (node (ref "R31") (pin "2") (pinfunction "2_2") (pintype "passive"))
      (node (ref "X2") (pin "24") (pinfunction "24_24") (pintype "passive"))
    )
    (net (code "120") (name "/O8") (class "Default")
      (node (ref "R32") (pin "2") (pinfunction "2_2") (pintype "passive"))
      (node (ref "X2") (pin "5") (pinfunction "5_5") (pintype "passive"))
    )
    (net (code "121") (name "/O9") (class "Default")
      (node (ref "R39") (pin "2") (pinfunction "2_2") (pintype "passive"))
      (node (ref "X2") (pin "25") (pinfunction "25_25") (pintype "passive"))
    )
    (net (code "122") (name "/O10") (class "Default")
      (node (ref "R40") (pin "2") (pinfunction "2_2") (pintype "passive"))
      (node (ref "X2") (pin "6") (pinfunction "6_6") (pintype "passive"))
    )
    (net (code "123") (name "/O11") (class "Default")
      (node (ref "R47") (pin "2") (pinfunction "2_2") (pintype "passive"))
      (node (ref "X2") (pin "8") (pinfunction "8_8") (pintype "passive"))
    )
    (net (code "124") (name "/O12") (class "Default")
      (node (ref "R48") (pin "2") (pinfunction "2_2") (pintype "passive"))
      (node (ref "X2") (pin "26") (pinfunction "26_26") (pintype "passive"))
    )
    (net (code "125") (name "/O13") (class "Default")
      (node (ref "R95") (pin "2") (pinfunction "2_2") (pintype "passive"))
      (node (ref "X2") (pin "34") (pinfunction "34_34") (pintype "passive"))
    )
    (net (code "126") (name "/O14") (class "Default")
      (node (ref "R96") (pin "2") (pinfunction "2_2") (pintype "passive"))
      (node (ref "X2") (pin "15") (pinfunction "15_15") (pintype "passive"))
    )
    (net (code "127") (name "/O15") (class "Default")
      (node (ref "R87") (pin "2") (pinfunction "2_2") (pintype "passive"))
      (node (ref "X2") (pin "14") (pinfunction "14_14") (pintype "passive"))
    )
    (net (code "128") (name "/O16") (class "Default")
      (node (ref "R88") (pin "2") (pinfunction "2_2") (pintype "passive"))
      (node (ref "X2") (pin "32") (pinfunction "32_32") (pintype "passive"))
    )
    (net (code "129") (name "/O17") (class "Default")
      (node (ref "R79") (pin "2") (pinfunction "2_2") (pintype "passive"))
      (node (ref "X2") (pin "13") (pinfunction "13_13") (pintype "passive"))
    )
    (net (code "130") (name "/O18") (class "Default")
      (node (ref "R80") (pin "2") (pinfunction "2_2") (pintype "passive"))
      (node (ref "X2") (pin "31") (pinfunction "31_31") (pintype "passive"))
    )
    (net (code "131") (name "/O19") (class "Default")
      (node (ref "R71") (pin "2") (pinfunction "2_2") (pintype "passive"))
      (node (ref "X2") (pin "30") (pinfunction "30_30") (pintype "passive"))
    )
    (net (code "132") (name "/O20") (class "Default")
      (node (ref "R72") (pin "2") (pinfunction "2_2") (pintype "passive"))
      (node (ref "X2") (pin "11") (pinfunction "11_11") (pintype "passive"))
    )
    (net (code "133") (name "/O21") (class "Default")
      (node (ref "R63") (pin "2") (pinfunction "2_2") (pintype "passive"))
      (node (ref "X2") (pin "29") (pinfunction "29_29") (pintype "passive"))
    )
    (net (code "134") (name "/O22") (class "Default")
      (node (ref "R64") (pin "2") (pinfunction "2_2") (pintype "passive"))
      (node (ref "X2") (pin "10") (pinfunction "10_10") (pintype "passive"))
    )
    (net (code "135") (name "/O23") (class "Default")
      (node (ref "R55") (pin "2") (pinfunction "2_2") (pintype "passive"))
      (node (ref "X2") (pin "9") (pinfunction "9_9") (pintype "passive"))
    )
    (net (code "136") (name "/O24") (class "Default")
      (node (ref "R56") (pin "2") (pinfunction "2_2") (pintype "passive"))
      (node (ref "X2") (pin "27") (pinfunction "27_27") (pintype "passive"))
    )
    (net (code "137") (name "/OUT1") (class "Default")
      (node (ref "IA2") (pin "15") (pinfunction "OUT1_15") (pintype "output"))
      (node (ref "R15") (pin "1") (pinfunction "1_1") (pintype "passive"))
    )
    (net (code "138") (name "/OUT2") (class "Default")
      (node (ref "IA2") (pin "14") (pinfunction "OUT2_14") (pintype "output"))
      (node (ref "R16") (pin "1") (pinfunction "1_1") (pintype "passive"))
    )
    (net (code "139") (name "/OUT3") (class "Default")
      (node (ref "IA1") (pin "15") (pinfunction "OUT1_15") (pintype "output"))
      (node (ref "R13") (pin "1") (pinfunction "1_1") (pintype "passive"))
    )
    (net (code "140") (name "/OUT4") (class "Default")
      (node (ref "IA1") (pin "14") (pinfunction "OUT2_14") (pintype "output"))
      (node (ref "R14") (pin "1") (pinfunction "1_1") (pintype "passive"))
    )
    (net (code "141") (name "/OUT5") (class "Default")
      (node (ref "IA3") (pin "15") (pinfunction "OUT1_15") (pintype "output"))
      (node (ref "R23") (pin "1") (pinfunction "1_1") (pintype "passive"))
    )
    (net (code "142") (name "/OUT6") (class "Default")
      (node (ref "IA3") (pin "14") (pinfunction "OUT2_14") (pintype "output"))
      (node (ref "R24") (pin "1") (pinfunction "1_1") (pintype "passive"))
    )
    (net (code "143") (name "/OUT7") (class "Default")
      (node (ref "IA4") (pin "15") (pinfunction "OUT1_15") (pintype "output"))
      (node (ref "R31") (pin "1") (pinfunction "1_1") (pintype "passive"))
    )
    (net (code "144") (name "/OUT8") (class "Default")
      (node (ref "IA4") (pin "14") (pinfunction "OUT2_14") (pintype "output"))
      (node (ref "R32") (pin "1") (pinfunction "1_1") (pintype "passive"))
    )
    (net (code "145") (name "/OUT9") (class "Default")
      (node (ref "IA5") (pin "15") (pinfunction "OUT1_15") (pintype "output"))
      (node (ref "R39") (pin "1") (pinfunction "1_1") (pintype "passive"))
    )
    (net (code "146") (name "/OUT10") (class "Default")
      (node (ref "IA5") (pin "14") (pinfunction "OUT2_14") (pintype "output"))
      (node (ref "R40") (pin "1") (pinfunction "1_1") (pintype "passive"))
    )
    (net (code "147") (name "/OUT11") (class "Default")
      (node (ref "IA6") (pin "15") (pinfunction "OUT1_15") (pintype "output"))
      (node (ref "R47") (pin "1") (pinfunction "1_1") (pintype "passive"))
    )
    (net (code "148") (name "/OUT12") (class "Default")
      (node (ref "IA6") (pin "14") (pinfunction "OUT2_14") (pintype "output"))
      (node (ref "R48") (pin "1") (pinfunction "1_1") (pintype "passive"))
    )
    (net (code "149") (name "/OUT13") (class "Default")
      (node (ref "IA12") (pin "15") (pinfunction "OUT1_15") (pintype "output"))
      (node (ref "R95") (pin "1") (pinfunction "1_1") (pintype "passive"))
    )
    (net (code "150") (name "/OUT14") (class "Default")
      (node (ref "IA12") (pin "14") (pinfunction "OUT2_14") (pintype "output"))
      (node (ref "R96") (pin "1") (pinfunction "1_1") (pintype "passive"))
    )
    (net (code "151") (name "/OUT15") (class "Default")
      (node (ref "IA11") (pin "15") (pinfunction "OUT1_15") (pintype "output"))
      (node (ref "R87") (pin "1") (pinfunction "1_1") (pintype "passive"))
    )
    (net (code "152") (name "/OUT16") (class "Default")
      (node (ref "IA11") (pin "14") (pinfunction "OUT2_14") (pintype "output"))
      (node (ref "R88") (pin "1") (pinfunction "1_1") (pintype "passive"))
    )
    (net (code "153") (name "/OUT17") (class "Default")
      (node (ref "IA10") (pin "15") (pinfunction "OUT1_15") (pintype "output"))
      (node (ref "R79") (pin "1") (pinfunction "1_1") (pintype "passive"))
    )
    (net (code "154") (name "/OUT18") (class "Default")
      (node (ref "IA10") (pin "14") (pinfunction "OUT2_14") (pintype "output"))
      (node (ref "R80") (pin "1") (pinfunction "1_1") (pintype "passive"))
    )
    (net (code "155") (name "/OUT19") (class "Default")
      (node (ref "IA9") (pin "15") (pinfunction "OUT1_15") (pintype "output"))
      (node (ref "R71") (pin "1") (pinfunction "1_1") (pintype "passive"))
    )
    (net (code "156") (name "/OUT20") (class "Default")
      (node (ref "IA9") (pin "14") (pinfunction "OUT2_14") (pintype "output"))
      (node (ref "R72") (pin "1") (pinfunction "1_1") (pintype "passive"))
    )
    (net (code "157") (name "/OUT21") (class "Default")
      (node (ref "IA8") (pin "15") (pinfunction "OUT1_15") (pintype "output"))
      (node (ref "R63") (pin "1") (pinfunction "1_1") (pintype "passive"))
    )
    (net (code "158") (name "/OUT22") (class "Default")
      (node (ref "IA8") (pin "14") (pinfunction "OUT2_14") (pintype "output"))
      (node (ref "R64") (pin "1") (pinfunction "1_1") (pintype "passive"))
    )
    (net (code "159") (name "/OUT23") (class "Default")
      (node (ref "IA7") (pin "15") (pinfunction "OUT1_15") (pintype "output"))
      (node (ref "R55") (pin "1") (pinfunction "1_1") (pintype "passive"))
    )
    (net (code "160") (name "/OUT24") (class "Default")
      (node (ref "IA7") (pin "14") (pinfunction "OUT2_14") (pintype "output"))
      (node (ref "R56") (pin "1") (pinfunction "1_1") (pintype "passive"))
    )
    (net (code "161") (name "/RG1") (class "Default")
      (node (ref "IA2") (pin "3") (pinfunction "RG1_3") (pintype "passive"))
      (node (ref "R11") (pin "1") (pinfunction "1_1") (pintype "passive"))
    )
    (net (code "162") (name "/RG1_2") (class "Default")
      (node (ref "IA2") (pin "2") (pinfunction "RG1_2_2") (pintype "passive"))
      (node (ref "R11") (pin "2") (pinfunction "2_2") (pintype "passive"))
    )
    (net (code "163") (name "/RG2") (class "Default")
      (node (ref "IA2") (pin "11") (pinfunction "RG2_11") (pintype "passive"))
      (node (ref "R12") (pin "1") (pinfunction "1_1") (pintype "passive"))
    )
    (net (code "164") (name "/RG2_2") (class "Default")
      (node (ref "IA2") (pin "10") (pinfunction "RG2_2_10") (pintype "passive"))
      (node (ref "R12") (pin "2") (pinfunction "2_2") (pintype "passive"))
    )
    (net (code "165") (name "/RG3") (class "Default")
      (node (ref "IA1") (pin "3") (pinfunction "RG1_3") (pintype "passive"))
      (node (ref "R1") (pin "1") (pinfunction "1_1") (pintype "passive"))
    )
    (net (code "166") (name "/RG3_2") (class "Default")
      (node (ref "IA1") (pin "2") (pinfunction "RG1_2_2") (pintype "passive"))
      (node (ref "R1") (pin "2") (pinfunction "2_2") (pintype "passive"))
    )
    (net (code "167") (name "/RG4") (class "Default")
      (node (ref "IA1") (pin "11") (pinfunction "RG2_11") (pintype "passive"))
      (node (ref "R2") (pin "1") (pinfunction "1_1") (pintype "passive"))
    )
    (net (code "168") (name "/RG4_2") (class "Default")
      (node (ref "IA1") (pin "10") (pinfunction "RG2_2_10") (pintype "passive"))
      (node (ref "R2") (pin "2") (pinfunction "2_2") (pintype "passive"))
    )
    (net (code "169") (name "/RG5") (class "Default")
      (node (ref "IA3") (pin "3") (pinfunction "RG1_3") (pintype "passive"))
      (node (ref "R17") (pin "1") (pinfunction "1_1") (pintype "passive"))
    )
    (net (code "170") (name "/RG5_2") (class "Default")
      (node (ref "IA3") (pin "2") (pinfunction "RG1_2_2") (pintype "passive"))
      (node (ref "R17") (pin "2") (pinfunction "2_2") (pintype "passive"))
    )
    (net (code "171") (name "/RG6") (class "Default")
      (node (ref "IA3") (pin "11") (pinfunction "RG2_11") (pintype "passive"))
      (node (ref "R18") (pin "1") (pinfunction "1_1") (pintype "passive"))
    )
    (net (code "172") (name "/RG6_2") (class "Default")
      (node (ref "IA3") (pin "10") (pinfunction "RG2_2_10") (pintype "passive"))
      (node (ref "R18") (pin "2") (pinfunction "2_2") (pintype "passive"))
    )
    (net (code "173") (name "/RG7") (class "Default")
      (node (ref "IA4") (pin "3") (pinfunction "RG1_3") (pintype "passive"))
      (node (ref "R25") (pin "1") (pinfunction "1_1") (pintype "passive"))
    )
    (net (code "174") (name "/RG7_2") (class "Default")
      (node (ref "IA4") (pin "2") (pinfunction "RG1_2_2") (pintype "passive"))
      (node (ref "R25") (pin "2") (pinfunction "2_2") (pintype "passive"))
    )
    (net (code "175") (name "/RG8") (class "Default")
      (node (ref "IA4") (pin "11") (pinfunction "RG2_11") (pintype "passive"))
      (node (ref "R26") (pin "1") (pinfunction "1_1") (pintype "passive"))
    )
    (net (code "176") (name "/RG8_2") (class "Default")
      (node (ref "IA4") (pin "10") (pinfunction "RG2_2_10") (pintype "passive"))
      (node (ref "R26") (pin "2") (pinfunction "2_2") (pintype "passive"))
    )
    (net (code "177") (name "/RG9") (class "Default")
      (node (ref "IA5") (pin "3") (pinfunction "RG1_3") (pintype "passive"))
      (node (ref "R33") (pin "1") (pinfunction "1_1") (pintype "passive"))
    )
    (net (code "178") (name "/RG9_2") (class "Default")
      (node (ref "IA5") (pin "2") (pinfunction "RG1_2_2") (pintype "passive"))
      (node (ref "R33") (pin "2") (pinfunction "2_2") (pintype "passive"))
    )
    (net (code "179") (name "/RG10") (class "Default")
      (node (ref "IA5") (pin "11") (pinfunction "RG2_11") (pintype "passive"))
      (node (ref "R34") (pin "1") (pinfunction "1_1") (pintype "passive"))
    )
    (net (code "180") (name "/RG10_2") (class "Default")
      (node (ref "IA5") (pin "10") (pinfunction "RG2_2_10") (pintype "passive"))
      (node (ref "R34") (pin "2") (pinfunction "2_2") (pintype "passive"))
    )
    (net (code "181") (name "/RG11") (class "Default")
      (node (ref "IA6") (pin "3") (pinfunction "RG1_3") (pintype "passive"))
      (node (ref "R41") (pin "1") (pinfunction "1_1") (pintype "passive"))
    )
    (net (code "182") (name "/RG11_2") (class "Default")
      (node (ref "IA6") (pin "2") (pinfunction "RG1_2_2") (pintype "passive"))
      (node (ref "R41") (pin "2") (pinfunction "2_2") (pintype "passive"))
    )
    (net (code "183") (name "/RG12") (class "Default")
      (node (ref "IA6") (pin "11") (pinfunction "RG2_11") (pintype "passive"))
      (node (ref "R42") (pin "1") (pinfunction "1_1") (pintype "passive"))
    )
    (net (code "184") (name "/RG12_2") (class "Default")
      (node (ref "IA6") (pin "10") (pinfunction "RG2_2_10") (pintype "passive"))
      (node (ref "R42") (pin "2") (pinfunction "2_2") (pintype "passive"))
    )
    (net (code "185") (name "/RG13") (class "Default")
      (node (ref "IA12") (pin "3") (pinfunction "RG1_3") (pintype "passive"))
      (node (ref "R89") (pin "1") (pinfunction "1_1") (pintype "passive"))
    )
    (net (code "186") (name "/RG13_2") (class "Default")
      (node (ref "IA12") (pin "2") (pinfunction "RG1_2_2") (pintype "passive"))
      (node (ref "R89") (pin "2") (pinfunction "2_2") (pintype "passive"))
    )
    (net (code "187") (name "/RG14") (class "Default")
      (node (ref "IA12") (pin "11") (pinfunction "RG2_11") (pintype "passive"))
      (node (ref "R90") (pin "1") (pinfunction "1_1") (pintype "passive"))
    )
    (net (code "188") (name "/RG14_2") (class "Default")
      (node (ref "IA12") (pin "10") (pinfunction "RG2_2_10") (pintype "passive"))
      (node (ref "R90") (pin "2") (pinfunction "2_2") (pintype "passive"))
    )
    (net (code "189") (name "/RG15") (class "Default")
      (node (ref "IA11") (pin "3") (pinfunction "RG1_3") (pintype "passive"))
      (node (ref "R81") (pin "1") (pinfunction "1_1") (pintype "passive"))
    )
    (net (code "190") (name "/RG15_2") (class "Default")
      (node (ref "IA11") (pin "2") (pinfunction "RG1_2_2") (pintype "passive"))
      (node (ref "R81") (pin "2") (pinfunction "2_2") (pintype "passive"))
    )
    (net (code "191") (name "/RG16") (class "Default")
      (node (ref "IA11") (pin "11") (pinfunction "RG2_11") (pintype "passive"))
      (node (ref "R82") (pin "1") (pinfunction "1_1") (pintype "passive"))
    )
    (net (code "192") (name "/RG16_2") (class "Default")
      (node (ref "IA11") (pin "10") (pinfunction "RG2_2_10") (pintype "passive"))
      (node (ref "R82") (pin "2") (pinfunction "2_2") (pintype "passive"))
    )
    (net (code "193") (name "/RG17") (class "Default")
      (node (ref "IA10") (pin "3") (pinfunction "RG1_3") (pintype "passive"))
      (node (ref "R73") (pin "1") (pinfunction "1_1") (pintype "passive"))
    )
    (net (code "194") (name "/RG17_2") (class "Default")
      (node (ref "IA10") (pin "2") (pinfunction "RG1_2_2") (pintype "passive"))
      (node (ref "R73") (pin "2") (pinfunction "2_2") (pintype "passive"))
    )
    (net (code "195") (name "/RG18") (class "Default")
      (node (ref "IA10") (pin "11") (pinfunction "RG2_11") (pintype "passive"))
      (node (ref "R74") (pin "1") (pinfunction "1_1") (pintype "passive"))
    )
    (net (code "196") (name "/RG18_2") (class "Default")
      (node (ref "IA10") (pin "10") (pinfunction "RG2_2_10") (pintype "passive"))
      (node (ref "R74") (pin "2") (pinfunction "2_2") (pintype "passive"))
    )
    (net (code "197") (name "/RG19") (class "Default")
      (node (ref "IA9") (pin "3") (pinfunction "RG1_3") (pintype "passive"))
      (node (ref "R65") (pin "1") (pinfunction "1_1") (pintype "passive"))
    )
    (net (code "198") (name "/RG19_2") (class "Default")
      (node (ref "IA9") (pin "2") (pinfunction "RG1_2_2") (pintype "passive"))
      (node (ref "R65") (pin "2") (pinfunction "2_2") (pintype "passive"))
    )
    (net (code "199") (name "/RG20") (class "Default")
      (node (ref "IA9") (pin "11") (pinfunction "RG2_11") (pintype "passive"))
      (node (ref "R66") (pin "1") (pinfunction "1_1") (pintype "passive"))
    )
    (net (code "200") (name "/RG20_2") (class "Default")
      (node (ref "IA9") (pin "10") (pinfunction "RG2_2_10") (pintype "passive"))
      (node (ref "R66") (pin "2") (pinfunction "2_2") (pintype "passive"))
    )
    (net (code "201") (name "/RG21") (class "Default")
      (node (ref "IA8") (pin "3") (pinfunction "RG1_3") (pintype "passive"))
      (node (ref "R57") (pin "1") (pinfunction "1_1") (pintype "passive"))
    )
    (net (code "202") (name "/RG21_2") (class "Default")
      (node (ref "IA8") (pin "2") (pinfunction "RG1_2_2") (pintype "passive"))
      (node (ref "R57") (pin "2") (pinfunction "2_2") (pintype "passive"))
    )
    (net (code "203") (name "/RG22") (class "Default")
      (node (ref "IA8") (pin "11") (pinfunction "RG2_11") (pintype "passive"))
      (node (ref "R58") (pin "1") (pinfunction "1_1") (pintype "passive"))
    )
    (net (code "204") (name "/RG22_2") (class "Default")
      (node (ref "IA8") (pin "10") (pinfunction "RG2_2_10") (pintype "passive"))
      (node (ref "R58") (pin "2") (pinfunction "2_2") (pintype "passive"))
    )
    (net (code "205") (name "/RG23") (class "Default")
      (node (ref "IA7") (pin "3") (pinfunction "RG1_3") (pintype "passive"))
      (node (ref "R49") (pin "1") (pinfunction "1_1") (pintype "passive"))
    )
    (net (code "206") (name "/RG23_2") (class "Default")
      (node (ref "IA7") (pin "2") (pinfunction "RG1_2_2") (pintype "passive"))
      (node (ref "R49") (pin "2") (pinfunction "2_2") (pintype "passive"))
    )
    (net (code "207") (name "/RG24") (class "Default")
      (node (ref "IA7") (pin "11") (pinfunction "RG2_11") (pintype "passive"))
      (node (ref "R50") (pin "1") (pinfunction "1_1") (pintype "passive"))
    )
    (net (code "208") (name "/RG24_2") (class "Default")
      (node (ref "IA7") (pin "10") (pinfunction "RG2_2_10") (pintype "passive"))
      (node (ref "R50") (pin "2") (pinfunction "2_2") (pintype "passive"))
    )
    (net (code "209") (name "/V+") (class "Default")
      (node (ref "C27") (pin "1") (pinfunction "1_1") (pintype "passive"))
      (node (ref "L1") (pin "1") (pinfunction "1_1") (pintype "passive"))
      (node (ref "U$3") (pin "7") (pinfunction "7_7") (pintype "passive"))
    )
    (net (code "210") (name "/VCC") (class "Default")
      (node (ref "C1") (pin "1") (pinfunction "1_1") (pintype "passive"))
      (node (ref "C10") (pin "1") (pinfunction "1_1") (pintype "passive"))
      (node (ref "C11") (pin "1") (pinfunction "1_1") (pintype "passive"))
      (node (ref "C12") (pin "1") (pinfunction "1_1") (pintype "passive"))
      (node (ref "C13") (pin "1") (pinfunction "1_1") (pintype "passive"))
      (node (ref "C14") (pin "1") (pinfunction "1_1") (pintype "passive"))
      (node (ref "C15") (pin "1") (pinfunction "1_1") (pintype "passive"))
      (node (ref "C16") (pin "1") (pinfunction "1_1") (pintype "passive"))
      (node (ref "C17") (pin "1") (pinfunction "1_1") (pintype "passive"))
      (node (ref "C18") (pin "1") (pinfunction "1_1") (pintype "passive"))
      (node (ref "C19") (pin "1") (pinfunction "1_1") (pintype "passive"))
      (node (ref "C20") (pin "1") (pinfunction "1_1") (pintype "passive"))
      (node (ref "C21") (pin "1") (pinfunction "1_1") (pintype "passive"))
      (node (ref "C22") (pin "1") (pinfunction "1_1") (pintype "passive"))
      (node (ref "C23") (pin "1") (pinfunction "1_1") (pintype "passive"))
      (node (ref "C24") (pin "1") (pinfunction "1_1") (pintype "passive"))
      (node (ref "C25") (pin "1") (pinfunction "1_1") (pintype "passive"))
      (node (ref "C26") (pin "1") (pinfunction "1_1") (pintype "passive"))
      (node (ref "C28") (pin "1") (pinfunction "1_1") (pintype "passive"))
      (node (ref "C3") (pin "1") (pinfunction "1_1") (pintype "passive"))
      (node (ref "C4") (pin "1") (pinfunction "1_1") (pintype "passive"))
      (node (ref "C5") (pin "1") (pinfunction "1_1") (pintype "passive"))
      (node (ref "C6") (pin "1") (pinfunction "1_1") (pintype "passive"))
      (node (ref "C7") (pin "1") (pinfunction "1_1") (pintype "passive"))
      (node (ref "C8") (pin "1") (pinfunction "1_1") (pintype "passive"))
      (node (ref "C9") (pin "1") (pinfunction "1_1") (pintype "passive"))
      (node (ref "IA1") (pin "16") (pinfunction "+VS_2_16") (pintype "power_in"))
      (node (ref "IA1") (pin "5") (pinfunction "+VS_5") (pintype "power_in"))
      (node (ref "IA10") (pin "16") (pinfunction "+VS_2_16") (pintype "power_in"))
      (node (ref "IA10") (pin "5") (pinfunction "+VS_5") (pintype "power_in"))
      (node (ref "IA11") (pin "16") (pinfunction "+VS_2_16") (pintype "power_in"))
      (node (ref "IA11") (pin "5") (pinfunction "+VS_5") (pintype "power_in"))
      (node (ref "IA12") (pin "16") (pinfunction "+VS_2_16") (pintype "power_in"))
      (node (ref "IA12") (pin "5") (pinfunction "+VS_5") (pintype "power_in"))
      (node (ref "IA2") (pin "16") (pinfunction "+VS_2_16") (pintype "power_in"))
      (node (ref "IA2") (pin "5") (pinfunction "+VS_5") (pintype "power_in"))
      (node (ref "IA3") (pin "16") (pinfunction "+VS_2_16") (pintype "power_in"))
      (node (ref "IA3") (pin "5") (pinfunction "+VS_5") (pintype "power_in"))
      (node (ref "IA4") (pin "16") (pinfunction "+VS_2_16") (pintype "power_in"))
      (node (ref "IA4") (pin "5") (pinfunction "+VS_5") (pintype "power_in"))
      (node (ref "IA5") (pin "16") (pinfunction "+VS_2_16") (pintype "power_in"))
      (node (ref "IA5") (pin "5") (pinfunction "+VS_5") (pintype "power_in"))
      (node (ref "IA6") (pin "16") (pinfunction "+VS_2_16") (pintype "power_in"))
      (node (ref "IA6") (pin "5") (pinfunction "+VS_5") (pintype "power_in"))
      (node (ref "IA7") (pin "16") (pinfunction "+VS_2_16") (pintype "power_in"))
      (node (ref "IA7") (pin "5") (pinfunction "+VS_5") (pintype "power_in"))
      (node (ref "IA8") (pin "16") (pinfunction "+VS_2_16") (pintype "power_in"))
      (node (ref "IA8") (pin "5") (pinfunction "+VS_5") (pintype "power_in"))
      (node (ref "IA9") (pin "16") (pinfunction "+VS_2_16") (pintype "power_in"))
      (node (ref "IA9") (pin "5") (pinfunction "+VS_5") (pintype "power_in"))
      (node (ref "L1") (pin "2") (pinfunction "2_2") (pintype "passive"))
      (node (ref "U1") (pin "3") (pinfunction "IN_3") (pintype "input"))
    )
    (net (code "211") (name "/VREF") (class "Default")
      (node (ref "IA1") (pin "6") (pinfunction "REF1_6") (pintype "input"))
      (node (ref "IA1") (pin "7") (pinfunction "REF2_7") (pintype "input"))
      (node (ref "IA10") (pin "6") (pinfunction "REF1_6") (pintype "input"))
      (node (ref "IA10") (pin "7") (pinfunction "REF2_7") (pintype "input"))
      (node (ref "IA11") (pin "6") (pinfunction "REF1_6") (pintype "input"))
      (node (ref "IA11") (pin "7") (pinfunction "REF2_7") (pintype "input"))
      (node (ref "IA12") (pin "6") (pinfunction "REF1_6") (pintype "input"))
      (node (ref "IA12") (pin "7") (pinfunction "REF2_7") (pintype "input"))
      (node (ref "IA2") (pin "6") (pinfunction "REF1_6") (pintype "input"))
      (node (ref "IA2") (pin "7") (pinfunction "REF2_7") (pintype "input"))
      (node (ref "IA3") (pin "6") (pinfunction "REF1_6") (pintype "input"))
      (node (ref "IA3") (pin "7") (pinfunction "REF2_7") (pintype "input"))
      (node (ref "IA4") (pin "6") (pinfunction "REF1_6") (pintype "input"))
      (node (ref "IA4") (pin "7") (pinfunction "REF2_7") (pintype "input"))
      (node (ref "IA5") (pin "6") (pinfunction "REF1_6") (pintype "input"))
      (node (ref "IA5") (pin "7") (pinfunction "REF2_7") (pintype "input"))
      (node (ref "IA6") (pin "6") (pinfunction "REF1_6") (pintype "input"))
      (node (ref "IA6") (pin "7") (pinfunction "REF2_7") (pintype "input"))
      (node (ref "IA7") (pin "6") (pinfunction "REF1_6") (pintype "input"))
      (node (ref "IA7") (pin "7") (pinfunction "REF2_7") (pintype "input"))
      (node (ref "IA8") (pin "6") (pinfunction "REF1_6") (pintype "input"))
      (node (ref "IA8") (pin "7") (pinfunction "REF2_7") (pintype "input"))
      (node (ref "IA9") (pin "6") (pinfunction "REF1_6") (pintype "input"))
      (node (ref "IA9") (pin "7") (pinfunction "REF2_7") (pintype "input"))
      (node (ref "U1") (pin "1") (pinfunction "OUT_1") (pintype "output"))
      (node (ref "X2") (pin "18") (pinfunction "18_18") (pintype "passive"))
    )
    (net (code "212") (name "Net-(U1-NOISE_REDUCTION)") (class "Default")
      (node (ref "C2") (pin "1") (pinfunction "1_1") (pintype "passive"))
      (node (ref "U1") (pin "8") (pinfunction "NOISE_REDUCTION_8") (pintype "passive"))
    )
    (net (code "213") (name "unconnected-(J1-Pad51)") (class "Default")
      (node (ref "J1") (pin "51") (pinfunction "51_51") (pintype "bidirectional"))
    )
    (net (code "214") (name "unconnected-(J1-Pad52)") (class "Default")
      (node (ref "J1") (pin "52") (pinfunction "52_52") (pintype "bidirectional"))
    )
    (net (code "215") (name "unconnected-(PAD1-P-Pad1)") (class "Default")
      (node (ref "PAD1") (pin "1") (pinfunction "P_1") (pintype "passive"))
    )
    (net (code "216") (name "unconnected-(PAD2-P-Pad1)") (class "Default")
      (node (ref "PAD2") (pin "1") (pinfunction "P_1") (pintype "passive"))
    )
    (net (code "217") (name "unconnected-(PAD3-P-Pad1)") (class "Default")
      (node (ref "PAD3") (pin "1") (pinfunction "P_1") (pintype "passive"))
    )
    (net (code "218") (name "unconnected-(PAD4-P-Pad1)") (class "Default")
      (node (ref "PAD4") (pin "1") (pinfunction "P_1") (pintype "passive"))
    )
    (net (code "219") (name "unconnected-(PAD5-P-Pad1)") (class "Default")
      (node (ref "PAD5") (pin "1") (pinfunction "P_1") (pintype "passive"))
    )
    (net (code "220") (name "unconnected-(PAD6-P-Pad1)") (class "Default")
      (node (ref "PAD6") (pin "1") (pinfunction "P_1") (pintype "passive"))
    )
    (net (code "221") (name "unconnected-(PAD7-P-Pad1)") (class "Default")
      (node (ref "PAD7") (pin "1") (pinfunction "P_1") (pintype "passive"))
    )
    (net (code "222") (name "unconnected-(PAD8-P-Pad1)") (class "Default")
      (node (ref "PAD8") (pin "1") (pinfunction "P_1") (pintype "passive"))
    )
    (net (code "223") (name "unconnected-(PAD9-P-Pad1)") (class "Default")
      (node (ref "PAD9") (pin "1") (pinfunction "P_1") (pintype "passive"))
    )
    (net (code "224") (name "unconnected-(PAD10-P-Pad1)") (class "Default")
      (node (ref "PAD10") (pin "1") (pinfunction "P_1") (pintype "passive"))
    )
    (net (code "225") (name "unconnected-(PAD11-P-Pad1)") (class "Default")
      (node (ref "PAD11") (pin "1") (pinfunction "P_1") (pintype "passive"))
    )
    (net (code "226") (name "unconnected-(PAD12-P-Pad1)") (class "Default")
      (node (ref "PAD12") (pin "1") (pinfunction "P_1") (pintype "passive"))
    )
    (net (code "227") (name "unconnected-(U1-NC-Pad6)") (class "Default")
      (node (ref "U1") (pin "6") (pinfunction "NC_6") (pintype "no_connect"))
    )
    (net (code "228") (name "unconnected-(U1-NC_2-Pad4)") (class "Default")
      (node (ref "U1") (pin "4") (pinfunction "NC_2_4") (pintype "no_connect"))
    )
    (net (code "229") (name "unconnected-(U1-NC_3-Pad5)") (class "Default")
      (node (ref "U1") (pin "5") (pinfunction "NC_3_5") (pintype "no_connect"))
    )
    (net (code "230") (name "unconnected-(U1-NC_4-Pad7)") (class "Default")
      (node (ref "U1") (pin "7") (pinfunction "NC_4_7") (pintype "no_connect"))
    )
    (net (code "231") (name "unconnected-(X2-PadG1)") (class "Default")
      (node (ref "X2") (pin "G1") (pinfunction "G1_G1") (pintype "passive"))
    )
    (net (code "232") (name "unconnected-(X2-PadG2)") (class "Default")
      (node (ref "X2") (pin "G2") (pinfunction "G2_G2") (pintype "passive"))
    )
  )
)
